# H7.net
KiCad netlist of a schematic drawn in Altium Designer
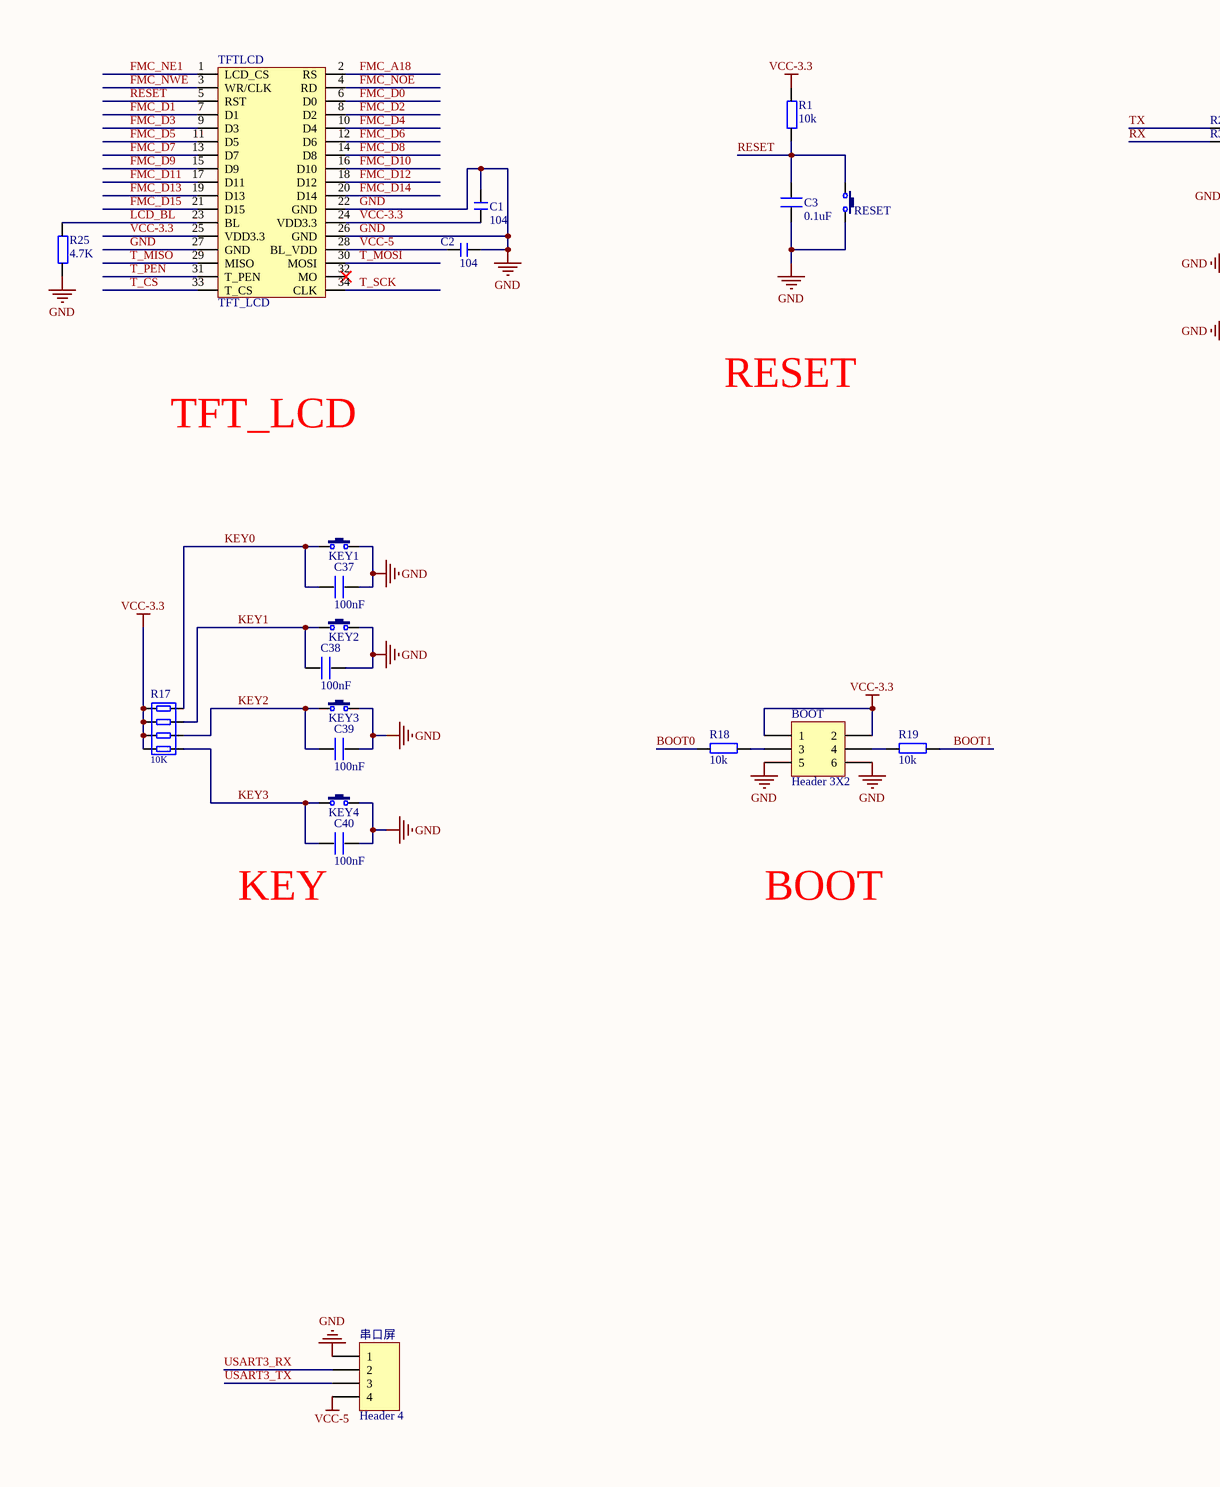
[diagram p0: H7.SchDoc, top left]
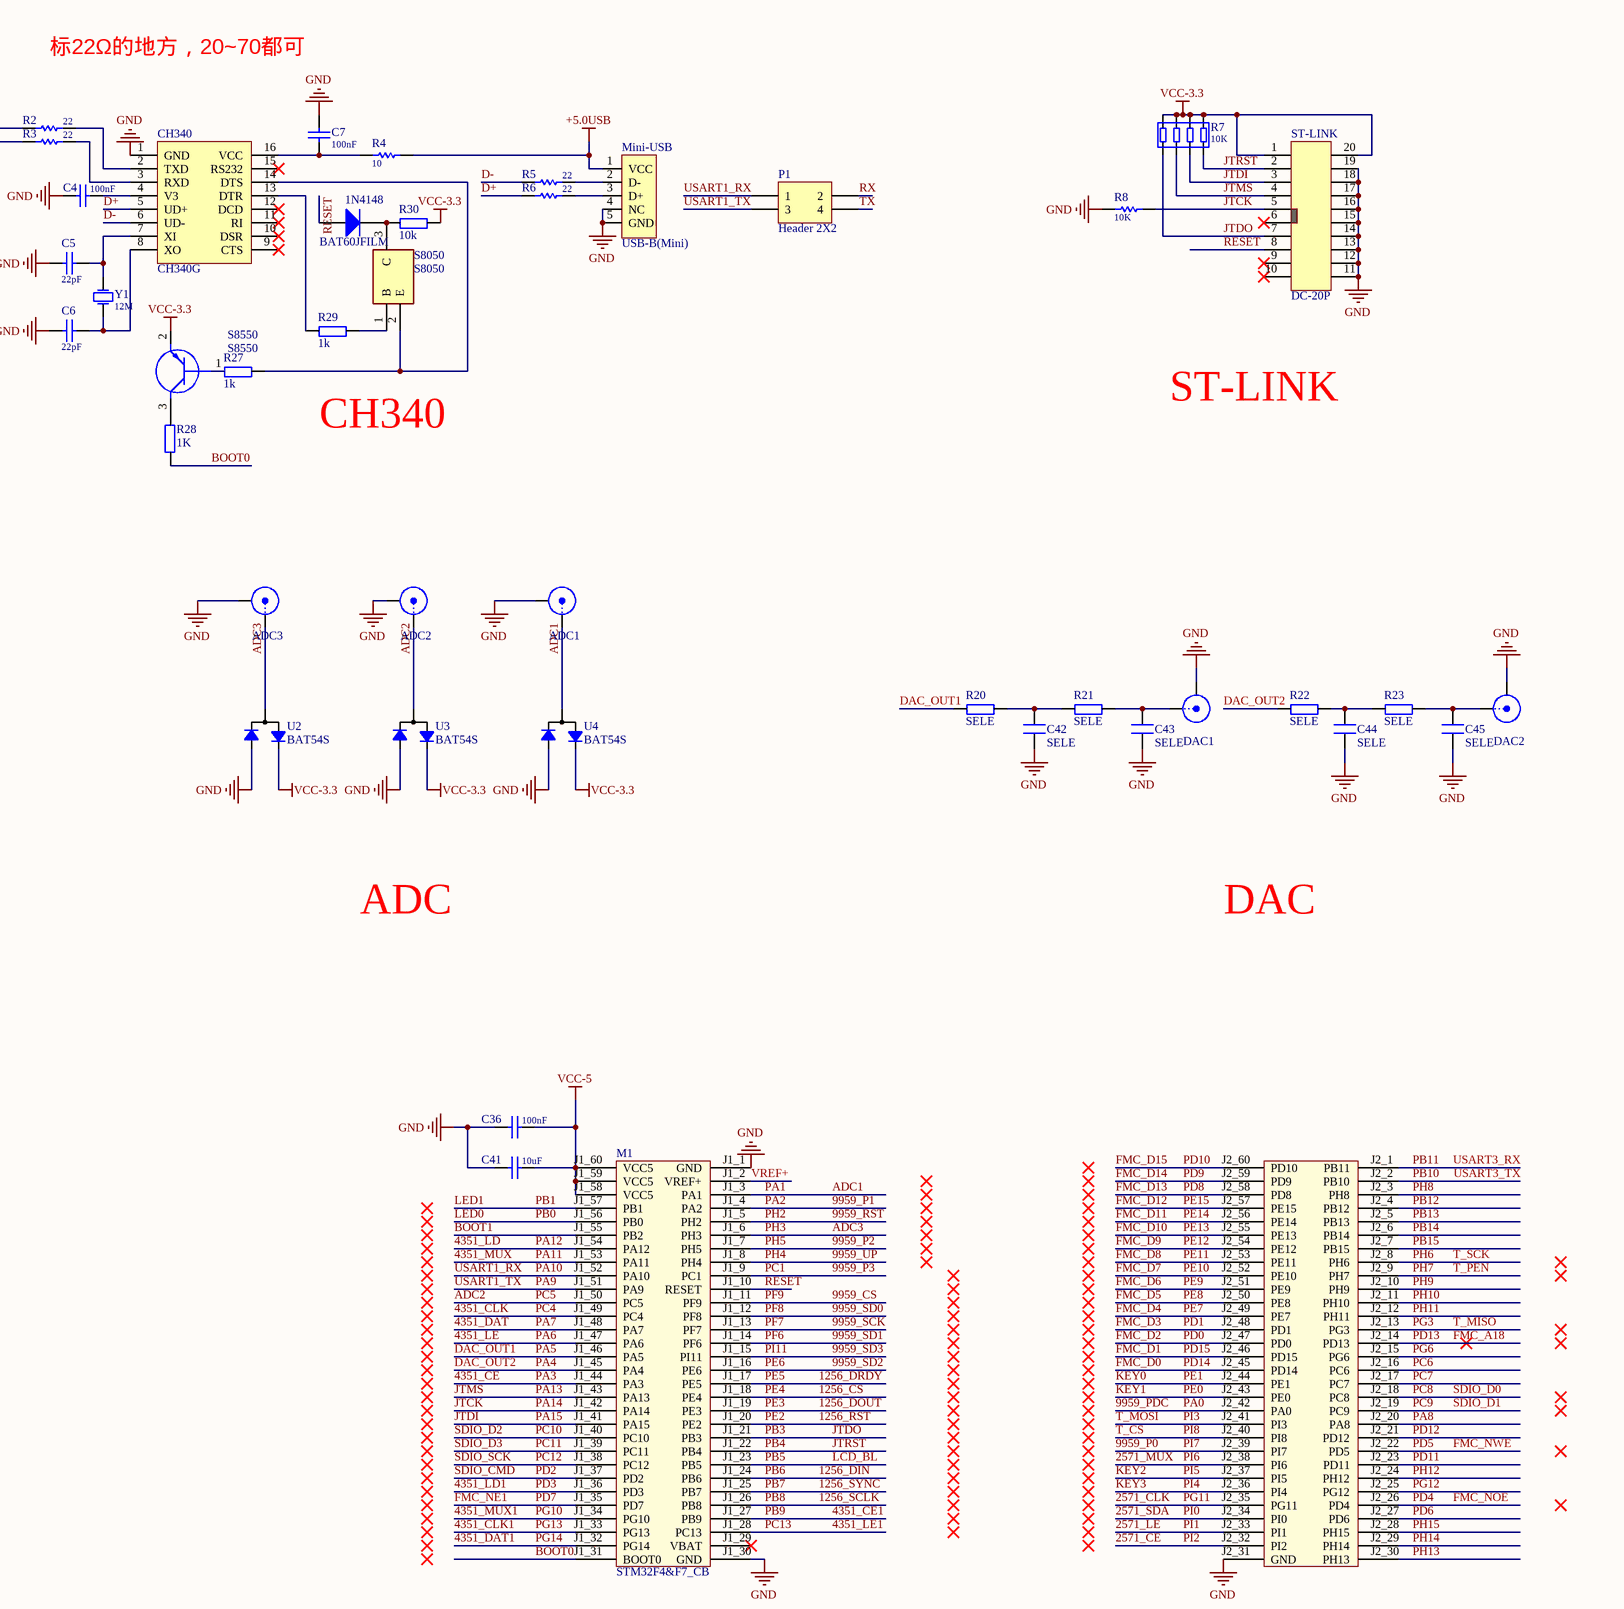
[diagram p1: H7.SchDoc, top middle]
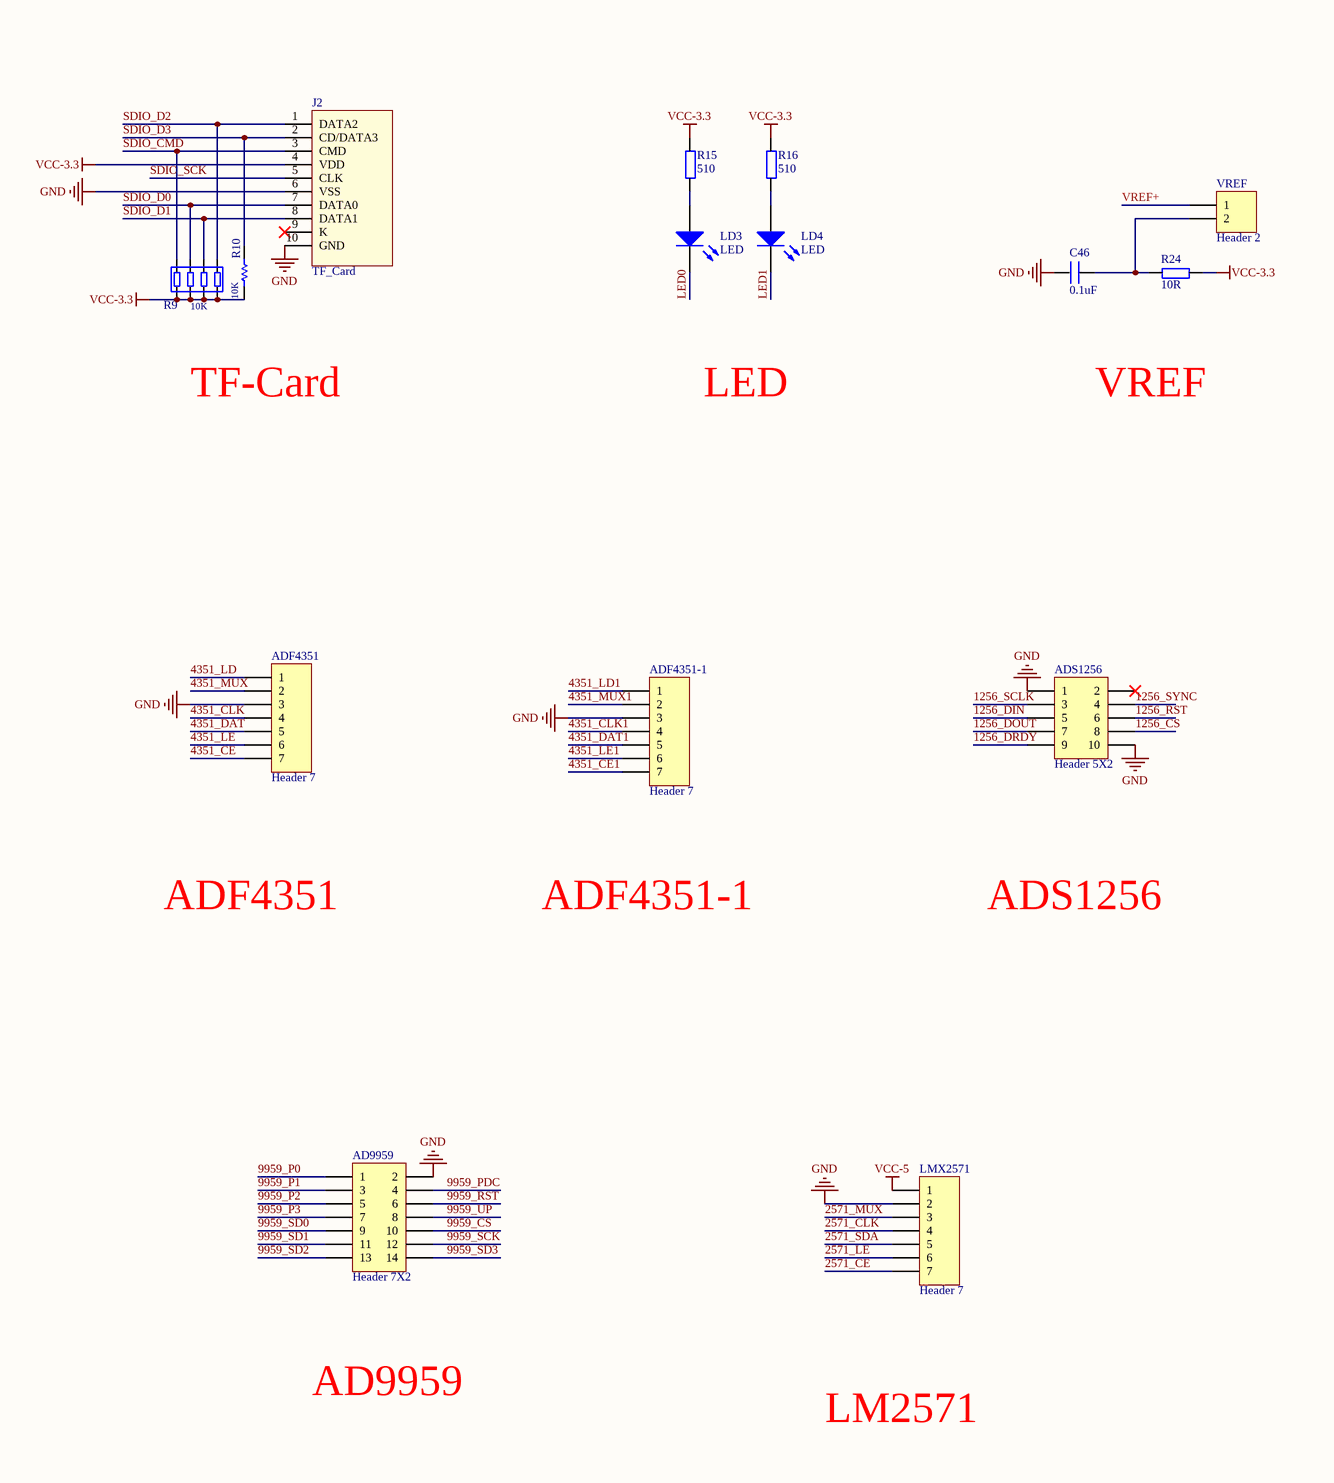
[diagram p2: H7.SchDoc, top right]
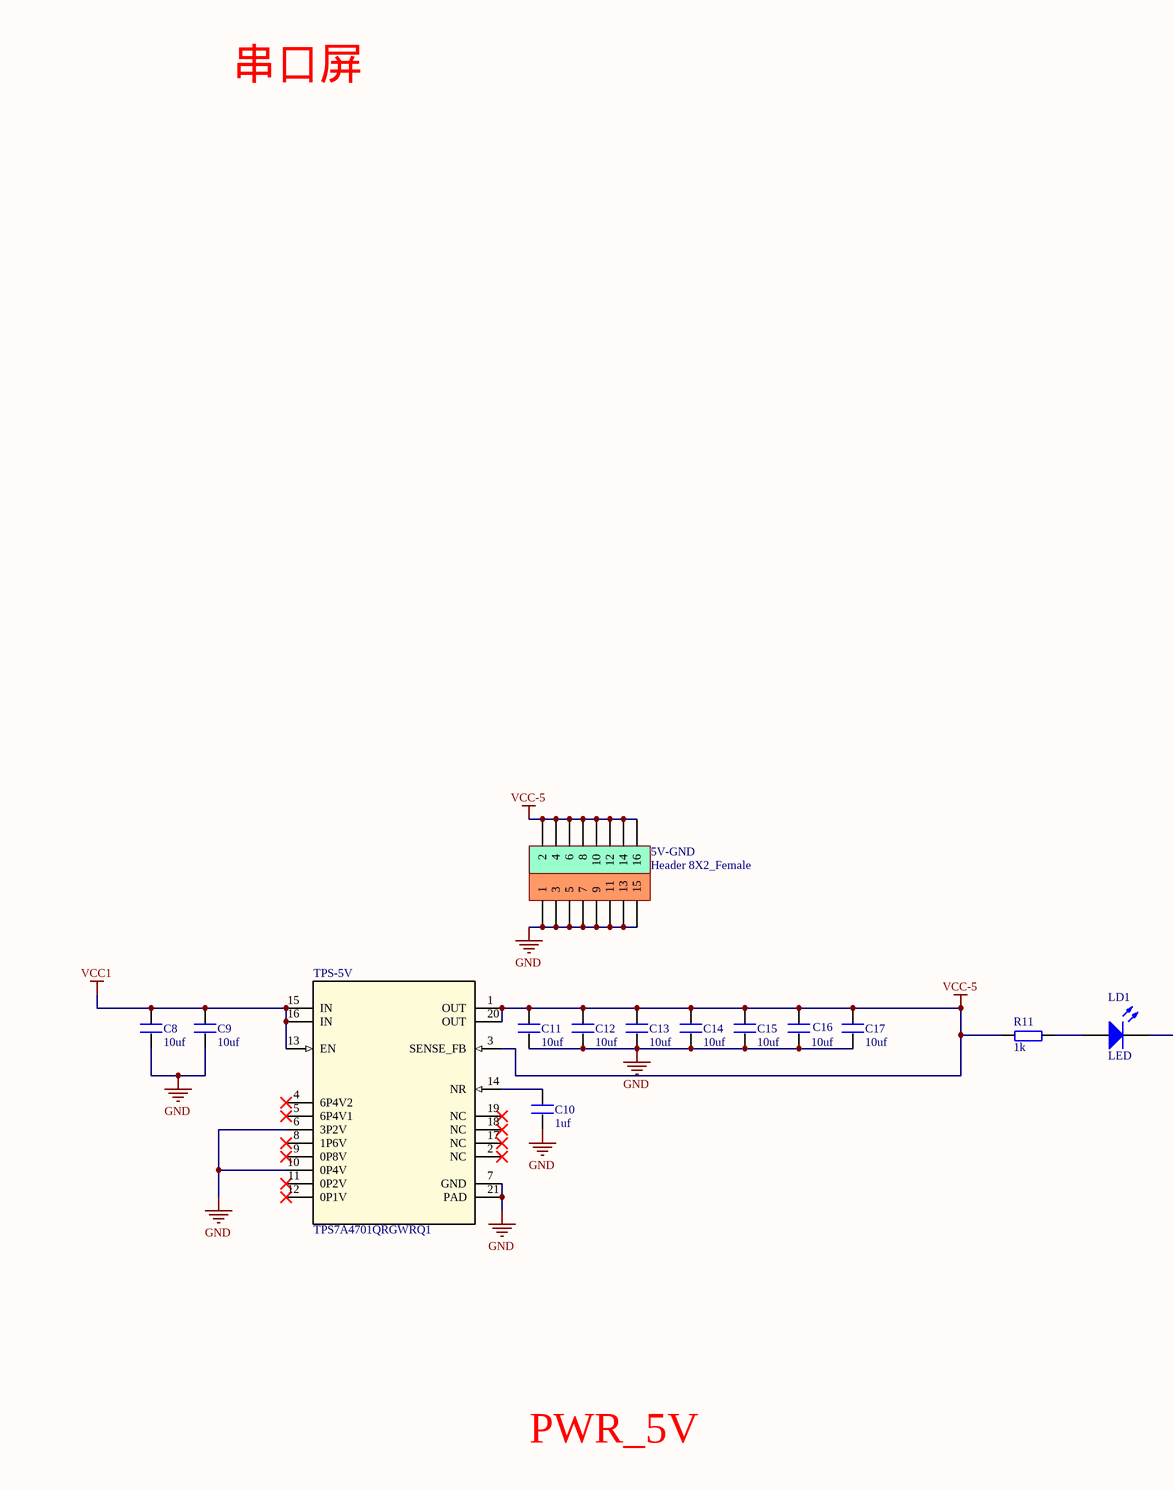
[diagram p3: H7.SchDoc, bottom left]
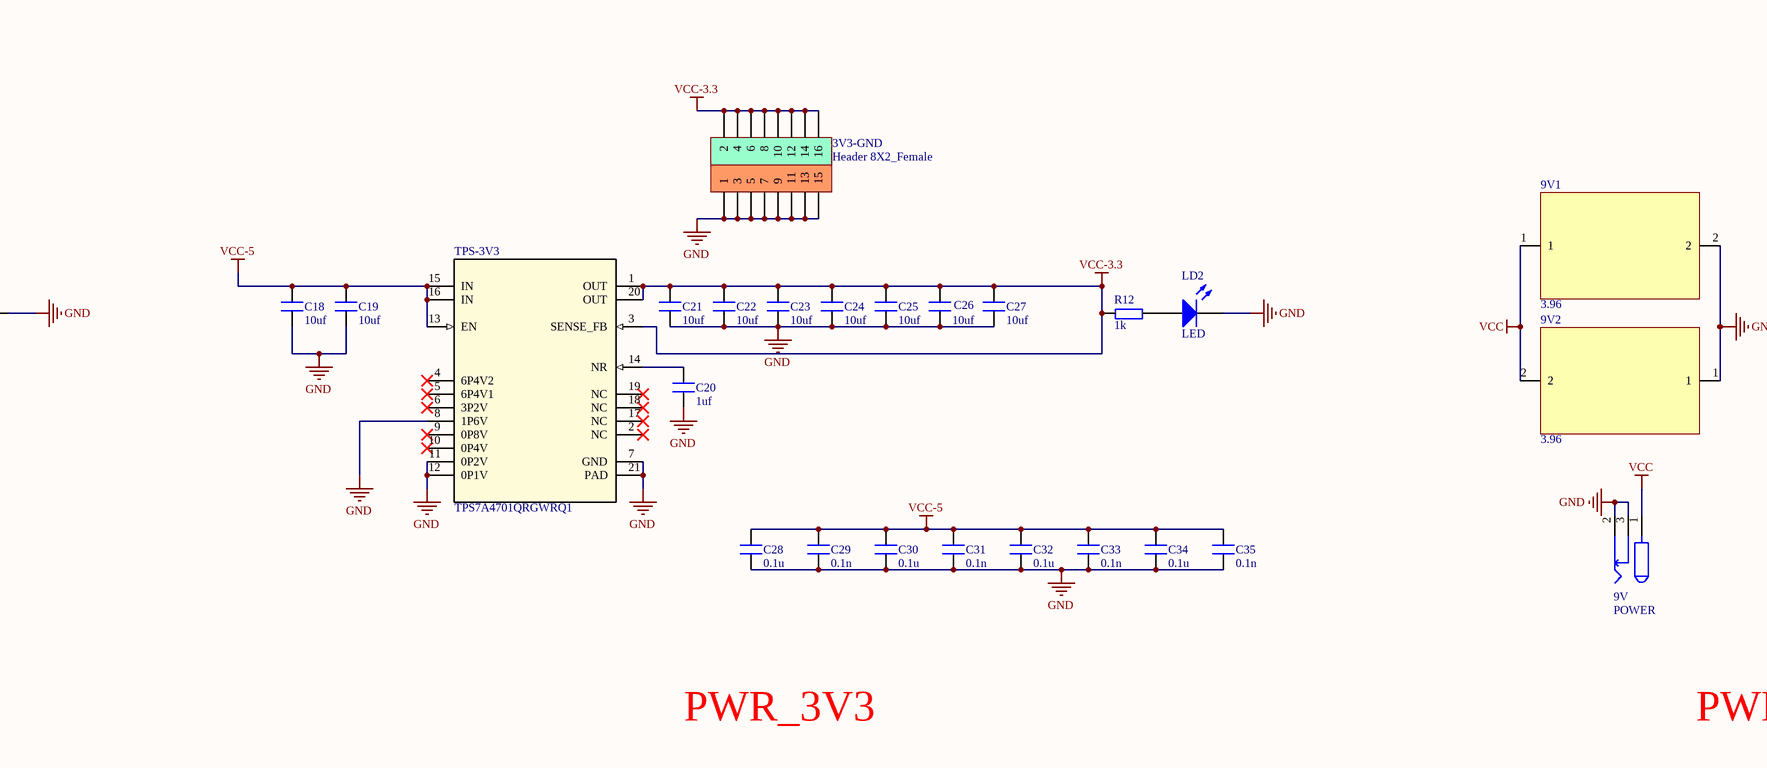
[diagram p4: H7.SchDoc, bottom middle]
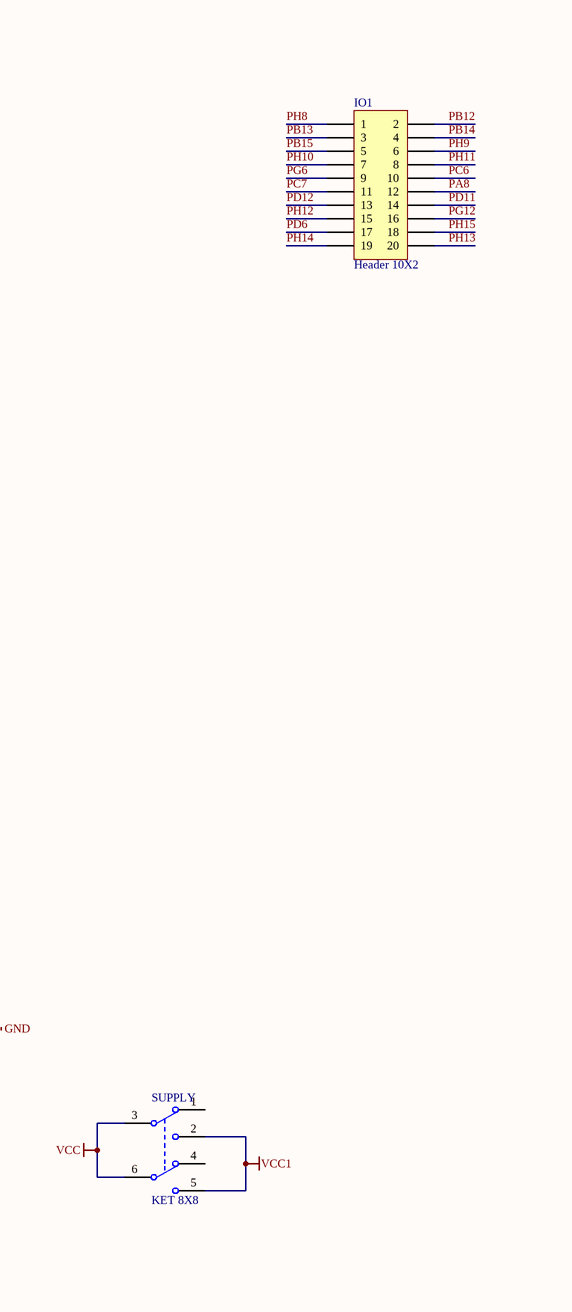
[diagram p5: H7.SchDoc, bottom right]

(export (version "E")
  (design (tool "Eeschema 10.0.6"))
  (components
    (comp (ref "1N4148")
      (value "BAT60JFILM")
      (footprint "DIODE_SOP")
      (description "Default Diode")
      (fields (field (name "PUBLISHER") "Altium Limited"))
      (libsource (lib "MYLIB") (part "Diode"))
    )
    (comp (ref "3V3-GND")
      (value "Header 8X2_Female")
      (footprint "HDR_8x2_2R54_V_F")
      (description "Header, 8-Pin, Dual row,female")
      (fields (field (name "PUBLISHER") "Altium Limited"))
      (libsource (lib "MYLIB") (part "Header 8X2_Female"))
    )
    (comp (ref "5V-GND")
      (value "Header 8X2_Female")
      (footprint "HDR_8x2_2R54_V_F")
      (description "Header, 8-Pin, Dual row,female")
      (fields (field (name "PUBLISHER") "Altium Limited"))
      (libsource (lib "MYLIB") (part "Header 8X2_Female"))
    )
    (comp (ref "9V") (value "POWER") (footprint "DC10B") (libsource (lib "MYLIB") (part "POW")))
    (comp (ref "9V1") (value "3.96") (footprint "3.96") (libsource (lib "MYLIB") (part "3.96")))
    (comp (ref "9V2") (value "3.96") (footprint "3.96") (libsource (lib "") (part "3.96_1")))
    (comp (ref "AD9959")
      (value "Header 7X2")
      (footprint "HDR2X7")
      (description "Header, 7-Pin, Dual row")
      (fields (field (name "PUBLISHER") "Altium Limited"))
      (libsource (lib "Miscellaneous Connectors") (part "Header 7X2"))
    )
    (comp (ref "ADC1")
      (value "SMA")
      (footprint "SMA")
      (description "SMA Connector")
      (libsource (lib "MYLIB") (part "SMA"))
    )
    (comp (ref "ADC2")
      (value "SMA")
      (footprint "SMA")
      (description "SMA Connector")
      (libsource (lib "MYLIB") (part "SMA"))
    )
    (comp (ref "ADC3")
      (value "SMA")
      (footprint "SMA")
      (description "SMA Connector")
      (libsource (lib "MYLIB") (part "SMA"))
    )
    (comp (ref "ADF4351")
      (value "Header 7")
      (footprint "HDR1X7")
      (description "Header, 7-Pin")
      (fields (field (name "PUBLISHER") "Altium Limited"))
      (libsource (lib "Miscellaneous Connectors") (part "Header 7"))
    )
    (comp (ref "ADF4351-1")
      (value "Header 7")
      (footprint "HDR1X7")
      (description "Header, 7-Pin")
      (fields (field (name "PUBLISHER") "Altium Limited"))
      (libsource (lib "Miscellaneous Connectors") (part "Header 7"))
    )
    (comp (ref "ADS1256")
      (value "Header 5X2")
      (footprint "HDR2X5")
      (description "Header, 5-Pin, Dual row")
      (fields (field (name "PUBLISHER") "Altium Limited"))
      (libsource (lib "Miscellaneous Connectors") (part "Header 5X2"))
    )
    (comp (ref "BOOT")
      (value "Header 3X2")
      (footprint "HDR2X3")
      (description "Header, 3-Pin, Dual row")
      (fields (field (name "PUBLISHER") "Altium Limited"))
      (libsource (lib "xz_C") (part "Header 3X2"))
    )
    (comp (ref "C1")
      (value "104")
      (footprint "0603C")
      (description "无极性贴片电容")
      (fields (field (name "版权归属") "源创客"))
      (libsource (lib "3.1   - 电阻-电容-电感") (part "C"))
    )
    (comp (ref "C2")
      (value "104")
      (footprint "0603C")
      (description "无极性贴片电容")
      (fields (field (name "版权归属") "源创客"))
      (libsource (lib "3.1   - 电阻-电容-电感") (part "C"))
    )
    (comp (ref "C3")
      (value "0.1uF")
      (footprint "0603C")
      (description "Capacitor")
      (libsource (lib "MYLIB") (part "C"))
    )
    (comp (ref "C4")
      (value "100nF")
      (footprint "0603C")
      (description "贴片瓷片电容")
      (fields (field (name "Comment") "Cap-S"))
      (libsource (lib "xz_D") (part "Cap-S"))
    )
    (comp (ref "C5")
      (value "22pF")
      (footprint "0603C")
      (description "贴片瓷片电容")
      (fields (field (name "Comment") "Cap-S"))
      (libsource (lib "xz_D") (part "Cap-S"))
    )
    (comp (ref "C6")
      (value "22pF")
      (footprint "0603C")
      (description "贴片瓷片电容")
      (fields (field (name "Comment") "Cap-S"))
      (libsource (lib "xz_D") (part "Cap-S"))
    )
    (comp (ref "C7")
      (value "100nF")
      (footprint "0603C")
      (description "贴片瓷片电容")
      (fields (field (name "Comment") "Cap-S"))
      (libsource (lib "xz_D") (part "Cap-S"))
    )
    (comp (ref "C8")
      (value "10uf")
      (footprint "0603C")
      (description "Capacitor")
      (libsource (lib "MYLIB") (part "C"))
    )
    (comp (ref "C9")
      (value "10uf")
      (footprint "0603C")
      (description "Capacitor")
      (libsource (lib "MYLIB") (part "C"))
    )
    (comp (ref "C10")
      (value "1uf")
      (footprint "0402")
      (description "Capacitor")
      (libsource (lib "MYLIB") (part "C"))
    )
    (comp (ref "C11")
      (value "10uf")
      (footprint "0603C")
      (description "Capacitor")
      (libsource (lib "MYLIB") (part "C"))
    )
    (comp (ref "C12")
      (value "10uf")
      (footprint "0603C")
      (description "Capacitor")
      (libsource (lib "MYLIB") (part "C"))
    )
    (comp (ref "C13")
      (value "10uf")
      (footprint "0603C")
      (description "Capacitor")
      (libsource (lib "MYLIB") (part "C"))
    )
    (comp (ref "C14")
      (value "10uf")
      (footprint "0603C")
      (description "Capacitor")
      (libsource (lib "MYLIB") (part "C"))
    )
    (comp (ref "C15")
      (value "10uf")
      (footprint "0603C")
      (description "Capacitor")
      (libsource (lib "MYLIB") (part "C"))
    )
    (comp (ref "C16")
      (value "10uf")
      (footprint "0603C")
      (description "Capacitor")
      (libsource (lib "MYLIB") (part "C"))
    )
    (comp (ref "C17")
      (value "10uf")
      (footprint "0603C")
      (description "Capacitor")
      (libsource (lib "MYLIB") (part "C"))
    )
    (comp (ref "C18")
      (value "10uf")
      (footprint "0603C")
      (description "Capacitor")
      (libsource (lib "MYLIB") (part "C"))
    )
    (comp (ref "C19")
      (value "10uf")
      (footprint "0603C")
      (description "Capacitor")
      (libsource (lib "MYLIB") (part "C"))
    )
    (comp (ref "C20")
      (value "1uf")
      (footprint "0402")
      (description "Capacitor")
      (libsource (lib "MYLIB") (part "C"))
    )
    (comp (ref "C21")
      (value "10uf")
      (footprint "0603C")
      (description "Capacitor")
      (libsource (lib "MYLIB") (part "C"))
    )
    (comp (ref "C22")
      (value "10uf")
      (footprint "0603C")
      (description "Capacitor")
      (libsource (lib "MYLIB") (part "C"))
    )
    (comp (ref "C23")
      (value "10uf")
      (footprint "0603C")
      (description "Capacitor")
      (libsource (lib "MYLIB") (part "C"))
    )
    (comp (ref "C24")
      (value "10uf")
      (footprint "0603C")
      (description "Capacitor")
      (libsource (lib "MYLIB") (part "C"))
    )
    (comp (ref "C25")
      (value "10uf")
      (footprint "0603C")
      (description "Capacitor")
      (libsource (lib "MYLIB") (part "C"))
    )
    (comp (ref "C26")
      (value "10uf")
      (footprint "0603C")
      (description "Capacitor")
      (libsource (lib "MYLIB") (part "C"))
    )
    (comp (ref "C27")
      (value "10uf")
      (footprint "0603C")
      (description "Capacitor")
      (libsource (lib "MYLIB") (part "C"))
    )
    (comp (ref "C28")
      (value "0.1u")
      (footprint "0402")
      (description "Capacitor")
      (libsource (lib "MYLIB") (part "C"))
    )
    (comp (ref "C29")
      (value "0.1n")
      (footprint "0402")
      (description "Capacitor")
      (libsource (lib "MYLIB") (part "C"))
    )
    (comp (ref "C30")
      (value "0.1u")
      (footprint "0402")
      (description "Capacitor")
      (libsource (lib "MYLIB") (part "C"))
    )
    (comp (ref "C31")
      (value "0.1n")
      (footprint "0402")
      (description "Capacitor")
      (libsource (lib "MYLIB") (part "C"))
    )
    (comp (ref "C32")
      (value "0.1u")
      (footprint "0402")
      (description "Capacitor")
      (libsource (lib "MYLIB") (part "C"))
    )
    (comp (ref "C33")
      (value "0.1n")
      (footprint "0402")
      (description "Capacitor")
      (libsource (lib "MYLIB") (part "C"))
    )
    (comp (ref "C34")
      (value "0.1u")
      (footprint "0402")
      (description "Capacitor")
      (libsource (lib "MYLIB") (part "C"))
    )
    (comp (ref "C35")
      (value "0.1n")
      (footprint "0402")
      (description "Capacitor")
      (libsource (lib "MYLIB") (part "C"))
    )
    (comp (ref "C36")
      (value "100nF")
      (footprint "C0603-L")
      (description "贴片瓷片电容")
      (fields (field (name "Comment") "Cap-S"))
      (libsource (lib "xz_D") (part "Cap-S"))
    )
    (comp (ref "C37")
      (value "100nF")
      (footprint "0603C")
      (description "Capacitor")
      (libsource (lib "MYLIB") (part "C"))
    )
    (comp (ref "C38")
      (value "100nF")
      (footprint "0603C")
      (description "Capacitor")
      (libsource (lib "MYLIB") (part "C"))
    )
    (comp (ref "C39")
      (value "100nF")
      (footprint "0603C")
      (description "Capacitor")
      (libsource (lib "MYLIB") (part "C"))
    )
    (comp (ref "C40")
      (value "100nF")
      (footprint "0603C")
      (description "Capacitor")
      (libsource (lib "MYLIB") (part "C"))
    )
    (comp (ref "C41")
      (value "10uF")
      (footprint "0603C")
      (description "贴片瓷片电容")
      (fields (field (name "Comment") "Cap-S"))
      (libsource (lib "xz_D") (part "Cap-S"))
    )
    (comp (ref "C42")
      (value "SELE")
      (footprint "0603C")
      (description "Capacitor")
      (libsource (lib "MYLIB") (part "C"))
    )
    (comp (ref "C43")
      (value "SELE")
      (footprint "0603C")
      (description "Capacitor")
      (libsource (lib "MYLIB") (part "C"))
    )
    (comp (ref "C44")
      (value "SELE")
      (footprint "0603C")
      (description "Capacitor")
      (libsource (lib "MYLIB") (part "C"))
    )
    (comp (ref "C45")
      (value "SELE")
      (footprint "0603C")
      (description "Capacitor")
      (libsource (lib "MYLIB") (part "C"))
    )
    (comp (ref "C46")
      (value "0.1uF")
      (footprint "0603C")
      (description "Capacitor")
      (libsource (lib "MYLIB") (part "C"))
    )
    (comp (ref "CH340")
      (value "CH340G")
      (footprint "SOP-16")
      (description "SOP16")
      (libsource (lib "CommonUsed") (part "CH340G"))
    )
    (comp (ref "DAC1")
      (value "SMA")
      (footprint "SMA")
      (description "SMA Connector")
      (libsource (lib "MYLIB") (part "SMA"))
    )
    (comp (ref "DAC2")
      (value "SMA")
      (footprint "SMA")
      (description "SMA Connector")
      (libsource (lib "MYLIB") (part "SMA"))
    )
    (comp (ref "IO1")
      (value "Header 10X2")
      (footprint "HDR2X10")
      (description "Header, 10-Pin, Dual row")
      (fields (field (name "PUBLISHER") "Altium Limited"))
      (libsource (lib "Miscellaneous Connectors") (part "Header 10X2"))
    )
    (comp (ref "J2")
      (value "TF_Card")
      (footprint "Micro SD")
      (description "TF卡座")
      (fields (field (name "版权归属") "源创客"))
      (libsource (lib "4.1   - 接口类") (part "TF_Card"))
    )
    (comp (ref "KEY1")
      (value "3x6x5")
      (footprint "TSW SMD-3*6*2.5")
      (description "3x6轻触开关")
      (fields (field (name "版权归属") "源创客"))
      (libsource (lib "") (part "TSW 3x6_1"))
    )
    (comp (ref "KEY2")
      (value "3x6x5")
      (footprint "TSW SMD-3*6*2.5")
      (description "3x6轻触开关")
      (fields (field (name "版权归属") "源创客"))
      (libsource (lib "") (part "TSW 3x6_1"))
    )
    (comp (ref "KEY3")
      (value "3x6x5")
      (footprint "TSW SMD-3*6*2.5")
      (description "3x6轻触开关")
      (fields (field (name "版权归属") "源创客"))
      (libsource (lib "") (part "TSW 3x6_1"))
    )
    (comp (ref "KEY4")
      (value "3x6x5")
      (footprint "TSW SMD-3*6*2.5")
      (description "3x6轻触开关")
      (fields (field (name "版权归属") "源创客"))
      (libsource (lib "") (part "TSW 3x6_1"))
    )
    (comp (ref "LD1")
      (value "LED")
      (footprint "SMDLED")
      (description "Typical RED, GREEN, YELLOW, AMBER GaAs LED")
      (fields (field (name "PUBLISHER") "Altium Limited"))
      (libsource (lib "MYLIB") (part "LED"))
    )
    (comp (ref "LD2")
      (value "LED")
      (footprint "SMDLED")
      (description "Typical RED, GREEN, YELLOW, AMBER GaAs LED")
      (fields (field (name "PUBLISHER") "Altium Limited"))
      (libsource (lib "MYLIB") (part "LED"))
    )
    (comp (ref "LD3")
      (value "LED")
      (footprint "SMDLED")
      (description "Typical RED, GREEN, YELLOW, AMBER GaAs LED")
      (fields (field (name "PUBLISHER") "Altium Limited"))
      (libsource (lib "MYLIB") (part "LED"))
    )
    (comp (ref "LD4")
      (value "LED")
      (footprint "SMDLED")
      (description "Typical RED, GREEN, YELLOW, AMBER GaAs LED")
      (fields (field (name "PUBLISHER") "Altium Limited"))
      (libsource (lib "MYLIB") (part "LED"))
    )
    (comp (ref "LMX2571")
      (value "Header 7")
      (footprint "HDR1X7")
      (description "Header, 7-Pin")
      (fields (field (name "PUBLISHER") "Altium Limited"))
      (libsource (lib "Miscellaneous Connectors") (part "Header 7"))
    )
    (comp (ref "M1")
      (value "STM32F4&F7_CB")
      (footprint "STM32F4&F7_CB - duplicate")
      (description "F429/746 Core Board")
      (libsource (lib "STM32H7-Board") (part "STM32F4&F7_CB"))
    )
    (comp (ref "Mini-USB")
      (value "USB-B(Mini)")
      (footprint "USB/SM0.8-6H5")
      (libsource (lib "MYLIB") (part "USB5"))
    )
    (comp (ref "P1")
      (value "Header 2X2")
      (footprint "HDR2X2")
      (description "Header, 2-Pin, Dual row")
      (fields (field (name "PUBLISHER") "Altium Limited"))
      (libsource (lib "MYLIB") (part "Header 2X2"))
    )
    (comp (ref "R1")
      (value "10k")
      (footprint "0603R")
      (description "Resistor")
      (libsource (lib "MYLIB") (part "Resistor"))
    )
    (comp (ref "R2")
      (value "22")
      (footprint "0603R")
      (description "贴片电阻")
      (fields (field (name "Comment") "R"))
      (libsource (lib "xz_D") (part "Res"))
    )
    (comp (ref "R3")
      (value "22")
      (footprint "0603R")
      (description "贴片电阻")
      (fields (field (name "Comment") "R"))
      (libsource (lib "xz_D") (part "Res"))
    )
    (comp (ref "R4")
      (value "10")
      (footprint "0603R")
      (description "贴片电阻")
      (fields (field (name "Comment") "R"))
      (libsource (lib "xz_D") (part "Res"))
    )
    (comp (ref "R5")
      (value "22")
      (footprint "0603R")
      (description "贴片电阻")
      (fields (field (name "Comment") "R"))
      (libsource (lib "xz_D") (part "Res"))
    )
    (comp (ref "R6")
      (value "22")
      (footprint "0603R")
      (description "贴片电阻")
      (fields (field (name "Comment") "R"))
      (libsource (lib "xz_D") (part "Res"))
    )
    (comp (ref "R7")
      (value "10K")
      (footprint "R0603X4")
      (description "排阻 4")
      (fields (field (name "Comment") "R"))
      (libsource (lib "xz_D") (part "Res-4R"))
    )
    (comp (ref "R8")
      (value "10K")
      (footprint "0603R")
      (description "贴片电阻")
      (fields (field (name "Comment") "R"))
      (libsource (lib "xz_D") (part "Res"))
    )
    (comp (ref "R9")
      (value "10K")
      (footprint "R0603X4")
      (description "排阻 4")
      (fields (field (name "Comment") "R"))
      (libsource (lib "xz_D") (part "Res-4R"))
    )
    (comp (ref "R10")
      (value "10K")
      (footprint "0603R")
      (description "贴片电阻")
      (fields (field (name "Comment") "R"))
      (libsource (lib "xz_D") (part "Res"))
    )
    (comp (ref "R11")
      (value "1k")
      (footprint "0603R")
      (description "Resistor")
      (libsource (lib "MYLIB") (part "Resistor"))
    )
    (comp (ref "R12")
      (value "1k")
      (footprint "0603R")
      (description "Resistor")
      (libsource (lib "MYLIB") (part "Resistor"))
    )
    (comp (ref "R15")
      (value "510")
      (footprint "0603R")
      (description "Resistor")
      (libsource (lib "MYLIB") (part "Resistor"))
    )
    (comp (ref "R16")
      (value "510")
      (footprint "0603R")
      (description "Resistor")
      (libsource (lib "MYLIB") (part "Resistor"))
    )
    (comp (ref "R17")
      (value "10K")
      (footprint "R0603X4")
      (description "排阻 4")
      (fields (field (name "Comment") "R"))
      (libsource (lib "xz_D") (part "Res-4R"))
    )
    (comp (ref "R18")
      (value "10k")
      (footprint "0603R")
      (description "Resistor")
      (libsource (lib "MYLIB") (part "Resistor"))
    )
    (comp (ref "R19")
      (value "10k")
      (footprint "0603R")
      (description "Resistor")
      (libsource (lib "MYLIB") (part "Resistor"))
    )
    (comp (ref "R20")
      (value "SELE")
      (footprint "0603R")
      (description "Resistor")
      (libsource (lib "MYLIB") (part "Resistor"))
    )
    (comp (ref "R21")
      (value "SELE")
      (footprint "0603R")
      (description "Resistor")
      (libsource (lib "MYLIB") (part "Resistor"))
    )
    (comp (ref "R22")
      (value "SELE")
      (footprint "0603R")
      (description "Resistor")
      (libsource (lib "MYLIB") (part "Resistor"))
    )
    (comp (ref "R23")
      (value "SELE")
      (footprint "0603R")
      (description "Resistor")
      (libsource (lib "MYLIB") (part "Resistor"))
    )
    (comp (ref "R24")
      (value "10R")
      (footprint "0603R")
      (description "Resistor")
      (libsource (lib "MYLIB") (part "Resistor"))
    )
    (comp (ref "R25")
      (value "4.7K")
      (footprint "0603R")
      (description "Resistor")
      (libsource (lib "MYLIB") (part "Resistor"))
    )
    (comp (ref "R27")
      (value "1k")
      (footprint "0603R")
      (description "Resistor")
      (libsource (lib "MYLIB") (part "Resistor"))
    )
    (comp (ref "R28")
      (value "1K")
      (footprint "0603R")
      (description "Resistor")
      (libsource (lib "MYLIB") (part "Resistor"))
    )
    (comp (ref "R29")
      (value "1k")
      (footprint "0603R")
      (description "Resistor")
      (libsource (lib "MYLIB") (part "Resistor"))
    )
    (comp (ref "R30")
      (value "10k")
      (footprint "0603R")
      (description "Resistor")
      (libsource (lib "MYLIB") (part "Resistor"))
    )
    (comp (ref "RESET")
      (value "3x6x5")
      (footprint "TSW SMD-3*6*2.5")
      (description "3x6轻触开关")
      (fields (field (name "版权归属") "源创客"))
      (libsource (lib "MYLIB") (part "TSW 3x6"))
    )
    (comp (ref "S8050")
      (value "S8050")
      (footprint "MYLIB:SOT95P240X115-3N")
      (description "Transistor")
      (libsource (lib "*") (part "S8050"))
    )
    (comp (ref "S8550")
      (value "S8550")
      (footprint "MYLIB:SOT95P240X115-3N")
      (description "Transistor BJT PNP")
      (libsource (lib "*") (part "S8550"))
    )
    (comp (ref "ST-LINK")
      (value "DC-20P")
      (footprint "DC-20P")
      (libsource (lib "CommonUsed") (part "DC-20P"))
    )
    (comp (ref "SUPPLY")
      (value "KET 8X8")
      (footprint "KFT DIP-8X8")
      (description "8*8自锁开关")
      (fields (field (name "版权归属") "源创客"))
      (libsource (lib "MYLIB") (part "KET 8X8"))
    )
    (comp (ref "TFTLCD")
      (value "TFT_LCD")
      (footprint "db2*17-4.3")
      (libsource (lib "MERCURY") (part "TFT_LCD"))
    )
    (comp (ref "TPS-3V3")
      (value "TPS7A4701QRGWRQ1")
      (footprint "RGW0020A")
      (description "No Description Available")
      (fields
        (field (name "MANUFACTURER") "Texas Instruments")
        (field (name "COPYRIGHT") "Copyright (C) 2018 Accelerated Designs. All rights reserved")
      )
      (libsource (lib "MYLIB") (part "TPS7A4701QRGWRQ1"))
    )
    (comp (ref "TPS-5V")
      (value "TPS7A4701QRGWRQ1")
      (footprint "RGW0020A")
      (description "No Description Available")
      (fields
        (field (name "MANUFACTURER") "Texas Instruments")
        (field (name "COPYRIGHT") "Copyright (C) 2018 Accelerated Designs. All rights reserved")
      )
      (libsource (lib "MYLIB") (part "TPS7A4701QRGWRQ1"))
    )
    (comp (ref "U2") (value "BAT54S") (footprint "SOT-23-3") (libsource (lib "xuxuxu") (part "BAT54S")))
    (comp (ref "U3") (value "BAT54S") (footprint "SOT-23-3") (libsource (lib "xuxuxu") (part "BAT54S")))
    (comp (ref "U4") (value "BAT54S") (footprint "SOT-23-3") (libsource (lib "xuxuxu") (part "BAT54S")))
    (comp (ref "VREF")
      (value "Header 2")
      (footprint "HDR1X2")
      (description "Header, 2-Pin")
      (fields (field (name "PUBLISHER") "Altium Limited"))
      (libsource (lib "Miscellaneous Connectors") (part "Header 2"))
    )
    (comp (ref "Y1")
      (value "12M")
      (footprint "XTAL-PB2-SMD")
      (description "晶振")
      (fields (field (name "Comment") "XTAL"))
      (libsource (lib "CommonUsed") (part "XTAL"))
    )
    (comp (ref "串口屏")
      (value "Header 4")
      (footprint "HDR1X4")
      (description "Header, 4-Pin")
      (fields (field (name "PUBLISHER") "Altium Limited"))
      (libsource (lib "Miscellaneous Connectors") (part "Header 4"))
    )
  )
  (nets
    (net (code "1") (name "+5.0USB") (class "Default")
      (node (ref "Mini-USB") (pin "1") (pinfunction "VCC_1") (pintype "passive"))
      (node (ref "R4") (pin "1") (pinfunction "1_1") (pintype "passive"))
    )
    (net (code "2") (name "/1256_CS") (class "Default")
      (node (ref "ADS1256") (pin "8") (pinfunction "8_8") (pintype "passive"))
      (node (ref "M1") (pin "J1_18") (pinfunction "PE4_J1_18") (pintype "passive"))
    )
    (net (code "3") (name "/1256_DIN") (class "Default")
      (node (ref "ADS1256") (pin "5") (pinfunction "5_5") (pintype "passive"))
      (node (ref "M1") (pin "J1_24") (pinfunction "PB6_J1_24") (pintype "passive"))
    )
    (net (code "4") (name "/1256_DOUT") (class "Default")
      (node (ref "ADS1256") (pin "7") (pinfunction "7_7") (pintype "passive"))
      (node (ref "M1") (pin "J1_19") (pinfunction "PE3_J1_19") (pintype "passive"))
    )
    (net (code "5") (name "/1256_DRDY") (class "Default")
      (node (ref "ADS1256") (pin "9") (pinfunction "9_9") (pintype "passive"))
      (node (ref "M1") (pin "J1_17") (pinfunction "PE5_J1_17") (pintype "passive"))
    )
    (net (code "6") (name "/1256_RST") (class "Default")
      (node (ref "ADS1256") (pin "6") (pinfunction "6_6") (pintype "passive"))
      (node (ref "M1") (pin "J1_20") (pinfunction "PE2_J1_20") (pintype "passive"))
    )
    (net (code "7") (name "/1256_SCLK") (class "Default")
      (node (ref "ADS1256") (pin "3") (pinfunction "3_3") (pintype "passive"))
      (node (ref "M1") (pin "J1_26") (pinfunction "PB8_J1_26") (pintype "passive"))
    )
    (net (code "8") (name "/1256_SYNC") (class "Default")
      (node (ref "ADS1256") (pin "4") (pinfunction "4_4") (pintype "passive"))
      (node (ref "M1") (pin "J1_25") (pinfunction "PB7_J1_25") (pintype "passive"))
    )
    (net (code "9") (name "/2571_CE") (class "Default")
      (node (ref "LMX2571") (pin "7") (pinfunction "7_7") (pintype "passive"))
      (node (ref "M1") (pin "J2_32") (pinfunction "PI2_J2_32") (pintype "passive"))
    )
    (net (code "10") (name "/2571_CLK") (class "Default")
      (node (ref "LMX2571") (pin "4") (pinfunction "4_4") (pintype "passive"))
      (node (ref "M1") (pin "J2_35") (pinfunction "PG11_J2_35") (pintype "passive"))
    )
    (net (code "11") (name "/2571_LE") (class "Default")
      (node (ref "LMX2571") (pin "6") (pinfunction "6_6") (pintype "passive"))
      (node (ref "M1") (pin "J2_33") (pinfunction "PI1_J2_33") (pintype "passive"))
    )
    (net (code "12") (name "/2571_MUX") (class "Default")
      (node (ref "LMX2571") (pin "3") (pinfunction "3_3") (pintype "passive"))
      (node (ref "M1") (pin "J2_38") (pinfunction "PI6_J2_38") (pintype "passive"))
    )
    (net (code "13") (name "/2571_SDA") (class "Default")
      (node (ref "LMX2571") (pin "5") (pinfunction "5_5") (pintype "passive"))
      (node (ref "M1") (pin "J2_34") (pinfunction "PI0_J2_34") (pintype "passive"))
    )
    (net (code "14") (name "/4351_CE") (class "Default")
      (node (ref "ADF4351") (pin "7") (pinfunction "7_7") (pintype "passive"))
      (node (ref "M1") (pin "J1_44") (pinfunction "PA3_J1_44") (pintype "passive"))
    )
    (net (code "15") (name "/4351_CE1") (class "Default")
      (node (ref "ADF4351-1") (pin "7") (pinfunction "7_7") (pintype "passive"))
      (node (ref "M1") (pin "J1_27") (pinfunction "PB9_J1_27") (pintype "passive"))
    )
    (net (code "16") (name "/4351_CLK") (class "Default")
      (node (ref "ADF4351") (pin "4") (pinfunction "4_4") (pintype "passive"))
      (node (ref "M1") (pin "J1_49") (pinfunction "PC4_J1_49") (pintype "passive"))
    )
    (net (code "17") (name "/4351_CLK1") (class "Default")
      (node (ref "ADF4351-1") (pin "4") (pinfunction "4_4") (pintype "passive"))
      (node (ref "M1") (pin "J1_33") (pinfunction "PG13_J1_33") (pintype "passive"))
    )
    (net (code "18") (name "/4351_DAT") (class "Default")
      (node (ref "ADF4351") (pin "5") (pinfunction "5_5") (pintype "passive"))
      (node (ref "M1") (pin "J1_48") (pinfunction "PA7_J1_48") (pintype "passive"))
    )
    (net (code "19") (name "/4351_DAT1") (class "Default")
      (node (ref "ADF4351-1") (pin "5") (pinfunction "5_5") (pintype "passive"))
      (node (ref "M1") (pin "J1_32") (pinfunction "PG14_J1_32") (pintype "passive"))
    )
    (net (code "20") (name "/4351_LD") (class "Default")
      (node (ref "ADF4351") (pin "1") (pinfunction "1_1") (pintype "passive"))
      (node (ref "M1") (pin "J1_54") (pinfunction "PA12_J1_54") (pintype "passive"))
    )
    (net (code "21") (name "/4351_LD1") (class "Default")
      (node (ref "ADF4351-1") (pin "1") (pinfunction "1_1") (pintype "passive"))
      (node (ref "M1") (pin "J1_36") (pinfunction "PD3_J1_36") (pintype "passive"))
    )
    (net (code "22") (name "/4351_LE") (class "Default")
      (node (ref "ADF4351") (pin "6") (pinfunction "6_6") (pintype "passive"))
      (node (ref "M1") (pin "J1_47") (pinfunction "PA6_J1_47") (pintype "passive"))
    )
    (net (code "23") (name "/4351_LE1") (class "Default")
      (node (ref "ADF4351-1") (pin "6") (pinfunction "6_6") (pintype "passive"))
      (node (ref "M1") (pin "J1_28") (pinfunction "PC13_J1_28") (pintype "passive"))
    )
    (net (code "24") (name "/4351_MUX") (class "Default")
      (node (ref "ADF4351") (pin "2") (pinfunction "2_2") (pintype "passive"))
      (node (ref "M1") (pin "J1_53") (pinfunction "PA11_J1_53") (pintype "passive"))
    )
    (net (code "25") (name "/4351_MUX1") (class "Default")
      (node (ref "ADF4351-1") (pin "2") (pinfunction "2_2") (pintype "passive"))
      (node (ref "M1") (pin "J1_34") (pinfunction "PG10_J1_34") (pintype "passive"))
    )
    (net (code "26") (name "/9959_CS") (class "Default")
      (node (ref "AD9959") (pin "10") (pinfunction "10_10") (pintype "passive"))
      (node (ref "M1") (pin "J1_11") (pinfunction "PF9_J1_11") (pintype "passive"))
    )
    (net (code "27") (name "/9959_P0") (class "Default")
      (node (ref "AD9959") (pin "1") (pinfunction "1_1") (pintype "passive"))
      (node (ref "M1") (pin "J2_39") (pinfunction "PI7_J2_39") (pintype "passive"))
    )
    (net (code "28") (name "/9959_P1") (class "Default")
      (node (ref "AD9959") (pin "3") (pinfunction "3_3") (pintype "passive"))
      (node (ref "M1") (pin "J1_4") (pinfunction "PA2_J1_4") (pintype "passive"))
    )
    (net (code "29") (name "/9959_P2") (class "Default")
      (node (ref "AD9959") (pin "5") (pinfunction "5_5") (pintype "passive"))
      (node (ref "M1") (pin "J1_7") (pinfunction "PH5_J1_7") (pintype "passive"))
    )
    (net (code "30") (name "/9959_P3") (class "Default")
      (node (ref "AD9959") (pin "7") (pinfunction "7_7") (pintype "passive"))
      (node (ref "M1") (pin "J1_9") (pinfunction "PC1_J1_9") (pintype "passive"))
    )
    (net (code "31") (name "/9959_PDC") (class "Default")
      (node (ref "AD9959") (pin "4") (pinfunction "4_4") (pintype "passive"))
      (node (ref "M1") (pin "J2_42") (pinfunction "PA0_J2_42") (pintype "passive"))
    )
    (net (code "32") (name "/9959_RST") (class "Default")
      (node (ref "AD9959") (pin "6") (pinfunction "6_6") (pintype "passive"))
      (node (ref "M1") (pin "J1_5") (pinfunction "PH2_J1_5") (pintype "passive"))
    )
    (net (code "33") (name "/9959_SCK") (class "Default")
      (node (ref "AD9959") (pin "12") (pinfunction "12_12") (pintype "passive"))
      (node (ref "M1") (pin "J1_13") (pinfunction "PF7_J1_13") (pintype "passive"))
    )
    (net (code "34") (name "/9959_SD0") (class "Default")
      (node (ref "AD9959") (pin "9") (pinfunction "9_9") (pintype "passive"))
      (node (ref "M1") (pin "J1_12") (pinfunction "PF8_J1_12") (pintype "passive"))
    )
    (net (code "35") (name "/9959_SD1") (class "Default")
      (node (ref "AD9959") (pin "11") (pinfunction "11_11") (pintype "passive"))
      (node (ref "M1") (pin "J1_14") (pinfunction "PF6_J1_14") (pintype "passive"))
    )
    (net (code "36") (name "/9959_SD2") (class "Default")
      (node (ref "AD9959") (pin "13") (pinfunction "13_13") (pintype "passive"))
      (node (ref "M1") (pin "J1_16") (pinfunction "PE6_J1_16") (pintype "passive"))
    )
    (net (code "37") (name "/9959_SD3") (class "Default")
      (node (ref "AD9959") (pin "14") (pinfunction "14_14") (pintype "passive"))
      (node (ref "M1") (pin "J1_15") (pinfunction "PI11_J1_15") (pintype "passive"))
    )
    (net (code "38") (name "/9959_UP") (class "Default")
      (node (ref "AD9959") (pin "8") (pinfunction "8_8") (pintype "passive"))
      (node (ref "M1") (pin "J1_8") (pinfunction "PH4_J1_8") (pintype "passive"))
    )
    (net (code "39") (name "/ADC1") (class "Default")
      (node (ref "ADC1") (pin "1") (pinfunction "X_1") (pintype "passive"))
      (node (ref "M1") (pin "J1_3") (pinfunction "PA1_J1_3") (pintype "passive"))
      (node (ref "U4") (pin "2") (pinfunction "2_2") (pintype "passive"))
    )
    (net (code "40") (name "/ADC2") (class "Default")
      (node (ref "ADC2") (pin "1") (pinfunction "X_1") (pintype "passive"))
      (node (ref "M1") (pin "J1_50") (pinfunction "PC5_J1_50") (pintype "passive"))
      (node (ref "U3") (pin "2") (pinfunction "2_2") (pintype "passive"))
    )
    (net (code "41") (name "/ADC3") (class "Default")
      (node (ref "ADC3") (pin "1") (pinfunction "X_1") (pintype "passive"))
      (node (ref "M1") (pin "J1_6") (pinfunction "PH3_J1_6") (pintype "passive"))
      (node (ref "U2") (pin "2") (pinfunction "2_2") (pintype "passive"))
    )
    (net (code "42") (name "/BOOT0") (class "Default")
      (node (ref "M1") (pin "J1_31") (pinfunction "BOOT0_J1_31") (pintype "passive"))
      (node (ref "R18") (pin "2") (pintype "passive"))
      (node (ref "R28") (pin "2") (pintype "passive"))
    )
    (net (code "43") (name "/BOOT1") (class "Default")
      (node (ref "M1") (pin "J1_55") (pinfunction "PB2_J1_55") (pintype "passive"))
      (node (ref "R19") (pin "1") (pintype "passive"))
    )
    (net (code "44") (name "/D+") (class "Default")
      (node (ref "CH340") (pin "5") (pinfunction "UD+_5") (pintype "passive"))
      (node (ref "R6") (pin "2") (pinfunction "2_2") (pintype "passive"))
    )
    (net (code "45") (name "/D-") (class "Default")
      (node (ref "CH340") (pin "6") (pinfunction "UD-_6") (pintype "passive"))
      (node (ref "R5") (pin "2") (pinfunction "2_2") (pintype "passive"))
    )
    (net (code "46") (name "/DAC_OUT1") (class "Default")
      (node (ref "M1") (pin "J1_46") (pinfunction "PA5_J1_46") (pintype "passive"))
      (node (ref "R20") (pin "1") (pintype "passive"))
    )
    (net (code "47") (name "/DAC_OUT2") (class "Default")
      (node (ref "M1") (pin "J1_45") (pinfunction "PA4_J1_45") (pintype "passive"))
      (node (ref "R22") (pin "1") (pintype "passive"))
    )
    (net (code "48") (name "/FMC_A18") (class "Default")
      (node (ref "M1") (pin "J2_14") (pinfunction "PD13_J2_14") (pintype "passive"))
      (node (ref "TFTLCD") (pin "2") (pinfunction "RS_2") (pintype "passive"))
    )
    (net (code "49") (name "/FMC_D0") (class "Default")
      (node (ref "M1") (pin "J2_45") (pinfunction "PD14_J2_45") (pintype "passive"))
      (node (ref "TFTLCD") (pin "6") (pinfunction "D0_6") (pintype "passive"))
    )
    (net (code "50") (name "/FMC_D1") (class "Default")
      (node (ref "M1") (pin "J2_46") (pinfunction "PD15_J2_46") (pintype "passive"))
      (node (ref "TFTLCD") (pin "7") (pinfunction "D1_7") (pintype "passive"))
    )
    (net (code "51") (name "/FMC_D2") (class "Default")
      (node (ref "M1") (pin "J2_47") (pinfunction "PD0_J2_47") (pintype "passive"))
      (node (ref "TFTLCD") (pin "8") (pinfunction "D2_8") (pintype "passive"))
    )
    (net (code "52") (name "/FMC_D3") (class "Default")
      (node (ref "M1") (pin "J2_48") (pinfunction "PD1_J2_48") (pintype "passive"))
      (node (ref "TFTLCD") (pin "9") (pinfunction "D3_9") (pintype "passive"))
    )
    (net (code "53") (name "/FMC_D4") (class "Default")
      (node (ref "M1") (pin "J2_49") (pinfunction "PE7_J2_49") (pintype "passive"))
      (node (ref "TFTLCD") (pin "10") (pinfunction "D4_10") (pintype "passive"))
    )
    (net (code "54") (name "/FMC_D5") (class "Default")
      (node (ref "M1") (pin "J2_50") (pinfunction "PE8_J2_50") (pintype "passive"))
      (node (ref "TFTLCD") (pin "11") (pinfunction "D5_11") (pintype "passive"))
    )
    (net (code "55") (name "/FMC_D6") (class "Default")
      (node (ref "M1") (pin "J2_51") (pinfunction "PE9_J2_51") (pintype "passive"))
      (node (ref "TFTLCD") (pin "12") (pinfunction "D6_12") (pintype "passive"))
    )
    (net (code "56") (name "/FMC_D7") (class "Default")
      (node (ref "M1") (pin "J2_52") (pinfunction "PE10_J2_52") (pintype "passive"))
      (node (ref "TFTLCD") (pin "13") (pinfunction "D7_13") (pintype "passive"))
    )
    (net (code "57") (name "/FMC_D8") (class "Default")
      (node (ref "M1") (pin "J2_53") (pinfunction "PE11_J2_53") (pintype "passive"))
      (node (ref "TFTLCD") (pin "14") (pinfunction "D8_14") (pintype "passive"))
    )
    (net (code "58") (name "/FMC_D9") (class "Default")
      (node (ref "M1") (pin "J2_54") (pinfunction "PE12_J2_54") (pintype "passive"))
      (node (ref "TFTLCD") (pin "15") (pinfunction "D9_15") (pintype "passive"))
    )
    (net (code "59") (name "/FMC_D10") (class "Default")
      (node (ref "M1") (pin "J2_55") (pinfunction "PE13_J2_55") (pintype "passive"))
      (node (ref "TFTLCD") (pin "16") (pinfunction "D10_16") (pintype "passive"))
    )
    (net (code "60") (name "/FMC_D11") (class "Default")
      (node (ref "M1") (pin "J2_56") (pinfunction "PE14_J2_56") (pintype "passive"))
      (node (ref "TFTLCD") (pin "17") (pinfunction "D11_17") (pintype "passive"))
    )
    (net (code "61") (name "/FMC_D12") (class "Default")
      (node (ref "M1") (pin "J2_57") (pinfunction "PE15_J2_57") (pintype "passive"))
      (node (ref "TFTLCD") (pin "18") (pinfunction "D12_18") (pintype "passive"))
    )
    (net (code "62") (name "/FMC_D13") (class "Default")
      (node (ref "M1") (pin "J2_58") (pinfunction "PD8_J2_58") (pintype "passive"))
      (node (ref "TFTLCD") (pin "19") (pinfunction "D13_19") (pintype "passive"))
    )
    (net (code "63") (name "/FMC_D14") (class "Default")
      (node (ref "M1") (pin "J2_59") (pinfunction "PD9_J2_59") (pintype "passive"))
      (node (ref "TFTLCD") (pin "20") (pinfunction "D14_20") (pintype "passive"))
    )
    (net (code "64") (name "/FMC_D15") (class "Default")
      (node (ref "M1") (pin "J2_60") (pinfunction "PD10_J2_60") (pintype "passive"))
      (node (ref "TFTLCD") (pin "21") (pinfunction "D15_21") (pintype "passive"))
    )
    (net (code "65") (name "/FMC_NE1") (class "Default")
      (node (ref "M1") (pin "J1_35") (pinfunction "PD7_J1_35") (pintype "passive"))
      (node (ref "TFTLCD") (pin "1") (pinfunction "LCD_CS_1") (pintype "passive"))
    )
    (net (code "66") (name "/FMC_NOE") (class "Default")
      (node (ref "M1") (pin "J2_26") (pinfunction "PD4_J2_26") (pintype "passive"))
      (node (ref "TFTLCD") (pin "4") (pinfunction "RD_4") (pintype "passive"))
    )
    (net (code "67") (name "/FMC_NWE") (class "Default")
      (node (ref "M1") (pin "J2_22") (pinfunction "PD5_J2_22") (pintype "passive"))
      (node (ref "TFTLCD") (pin "3") (pinfunction "WR/CLK_3") (pintype "passive"))
    )
    (net (code "68") (name "/JTCK") (class "Default")
      (node (ref "M1") (pin "J1_42") (pinfunction "PA14_J1_42") (pintype "passive"))
      (node (ref "R8") (pin "1") (pinfunction "1_1") (pintype "passive"))
      (node (ref "ST-LINK") (pin "5") (pinfunction "5_5") (pintype "passive"))
    )
    (net (code "69") (name "/JTDI") (class "Default")
      (node (ref "M1") (pin "J1_41") (pinfunction "PA15_J1_41") (pintype "passive"))
      (node (ref "R7") (pin "3") (pintype "passive"))
      (node (ref "ST-LINK") (pin "3") (pinfunction "3_3") (pintype "passive"))
    )
    (net (code "70") (name "/JTDO") (class "Default")
      (node (ref "M1") (pin "J1_21") (pinfunction "PB3_J1_21") (pintype "passive"))
      (node (ref "R7") (pin "1") (pintype "passive"))
      (node (ref "ST-LINK") (pin "7") (pinfunction "7_7") (pintype "passive"))
    )
    (net (code "71") (name "/JTMS") (class "Default")
      (node (ref "M1") (pin "J1_43") (pinfunction "PA13_J1_43") (pintype "passive"))
      (node (ref "R7") (pin "2") (pintype "passive"))
      (node (ref "ST-LINK") (pin "4") (pinfunction "4_4") (pintype "passive"))
    )
    (net (code "72") (name "/JTRST") (class "Default")
      (node (ref "M1") (pin "J1_22") (pinfunction "PB4_J1_22") (pintype "passive"))
      (node (ref "R7") (pin "4") (pintype "passive"))
      (node (ref "ST-LINK") (pin "2") (pinfunction "2_2") (pintype "passive"))
    )
    (net (code "73") (name "/KEY0") (class "Default")
      (node (ref "C37") (pin "1") (pintype "passive"))
      (node (ref "KEY1") (pin "1") (pinfunction "1_1") (pintype "passive"))
      (node (ref "M1") (pin "J2_44") (pinfunction "PE1_J2_44") (pintype "passive"))
      (node (ref "R17") (pin "4") (pintype "passive"))
    )
    (net (code "74") (name "/KEY1") (class "Default")
      (node (ref "C38") (pin "1") (pintype "passive"))
      (node (ref "KEY2") (pin "1") (pinfunction "1_1") (pintype "passive"))
      (node (ref "M1") (pin "J2_43") (pinfunction "PE0_J2_43") (pintype "passive"))
      (node (ref "R17") (pin "3") (pintype "passive"))
    )
    (net (code "75") (name "/KEY2") (class "Default")
      (node (ref "C39") (pin "1") (pintype "passive"))
      (node (ref "KEY3") (pin "1") (pinfunction "1_1") (pintype "passive"))
      (node (ref "M1") (pin "J2_37") (pinfunction "PI5_J2_37") (pintype "passive"))
      (node (ref "R17") (pin "2") (pintype "passive"))
    )
    (net (code "76") (name "/KEY3") (class "Default")
      (node (ref "C40") (pin "1") (pintype "passive"))
      (node (ref "KEY4") (pin "1") (pinfunction "1_1") (pintype "passive"))
      (node (ref "M1") (pin "J2_36") (pinfunction "PI4_J2_36") (pintype "passive"))
      (node (ref "R17") (pin "1") (pintype "passive"))
    )
    (net (code "77") (name "/LCD_BL") (class "Default")
      (node (ref "M1") (pin "J1_23") (pinfunction "PB5_J1_23") (pintype "passive"))
      (node (ref "R25") (pin "2") (pintype "passive"))
      (node (ref "TFTLCD") (pin "23") (pinfunction "BL_23") (pintype "passive"))
    )
    (net (code "78") (name "/LED0") (class "Default")
      (node (ref "LD3") (pin "2") (pinfunction "K_2") (pintype "passive"))
      (node (ref "M1") (pin "J1_56") (pinfunction "PB0_J1_56") (pintype "passive"))
    )
    (net (code "79") (name "/LED1") (class "Default")
      (node (ref "LD4") (pin "2") (pinfunction "K_2") (pintype "passive"))
      (node (ref "M1") (pin "J1_57") (pinfunction "PB1_J1_57") (pintype "passive"))
    )
    (net (code "80") (name "/PA8") (class "Default")
      (node (ref "IO1") (pin "12") (pinfunction "12_12") (pintype "passive"))
      (node (ref "M1") (pin "J2_20") (pinfunction "PA8_J2_20") (pintype "passive"))
    )
    (net (code "81") (name "/PA9") (class "Default")
      (node (ref "M1") (pin "J1_51") (pinfunction "PA9_J1_51") (pintype "passive"))
      (node (ref "P1") (pin "3") (pinfunction "3_3") (pintype "passive"))
    )
    (net (code "82") (name "/PA10") (class "Default")
      (node (ref "M1") (pin "J1_52") (pinfunction "PA10_J1_52") (pintype "passive"))
      (node (ref "P1") (pin "1") (pinfunction "1_1") (pintype "passive"))
    )
    (net (code "83") (name "/PB10") (class "Default")
      (node (ref "M1") (pin "J2_2") (pinfunction "PB10_J2_2") (pintype "passive"))
      (node (ref "串口屏") (pin "3") (pinfunction "3_3") (pintype "passive"))
    )
    (net (code "84") (name "/PB11") (class "Default")
      (node (ref "M1") (pin "J2_1") (pinfunction "PB11_J2_1") (pintype "passive"))
      (node (ref "串口屏") (pin "2") (pinfunction "2_2") (pintype "passive"))
    )
    (net (code "85") (name "/PB12") (class "Default")
      (node (ref "IO1") (pin "2") (pinfunction "2_2") (pintype "passive"))
      (node (ref "M1") (pin "J2_4") (pinfunction "PB12_J2_4") (pintype "passive"))
    )
    (net (code "86") (name "/PB13") (class "Default")
      (node (ref "IO1") (pin "3") (pinfunction "3_3") (pintype "passive"))
      (node (ref "M1") (pin "J2_5") (pinfunction "PB13_J2_5") (pintype "passive"))
    )
    (net (code "87") (name "/PB14") (class "Default")
      (node (ref "IO1") (pin "4") (pinfunction "4_4") (pintype "passive"))
      (node (ref "M1") (pin "J2_6") (pinfunction "PB14_J2_6") (pintype "passive"))
    )
    (net (code "88") (name "/PB15") (class "Default")
      (node (ref "IO1") (pin "5") (pinfunction "5_5") (pintype "passive"))
      (node (ref "M1") (pin "J2_7") (pinfunction "PB15_J2_7") (pintype "passive"))
    )
    (net (code "89") (name "/PC6") (class "Default")
      (node (ref "IO1") (pin "10") (pinfunction "10_10") (pintype "passive"))
      (node (ref "M1") (pin "J2_16") (pinfunction "PC6_J2_16") (pintype "passive"))
    )
    (net (code "90") (name "/PC7") (class "Default")
      (node (ref "IO1") (pin "11") (pinfunction "11_11") (pintype "passive"))
      (node (ref "M1") (pin "J2_17") (pinfunction "PC7_J2_17") (pintype "passive"))
    )
    (net (code "91") (name "/PC8") (class "Default")
      (node (ref "J2") (pin "7") (pinfunction "DATA0_7") (pintype "passive"))
      (node (ref "M1") (pin "J2_18") (pinfunction "PC8_J2_18") (pintype "passive"))
      (node (ref "R9") (pin "7") (pintype "passive"))
    )
    (net (code "92") (name "/PC9") (class "Default")
      (node (ref "J2") (pin "8") (pinfunction "DATA1_8") (pintype "passive"))
      (node (ref "M1") (pin "J2_19") (pinfunction "PC9_J2_19") (pintype "passive"))
      (node (ref "R9") (pin "6") (pintype "passive"))
    )
    (net (code "93") (name "/PC10") (class "Default")
      (node (ref "J2") (pin "1") (pinfunction "DATA2_1") (pintype "passive"))
      (node (ref "M1") (pin "J1_40") (pinfunction "PC10_J1_40") (pintype "passive"))
      (node (ref "R9") (pin "5") (pintype "passive"))
    )
    (net (code "94") (name "/PC11") (class "Default")
      (node (ref "J2") (pin "2") (pinfunction "CD/DATA3_2") (pintype "passive"))
      (node (ref "M1") (pin "J1_39") (pinfunction "PC11_J1_39") (pintype "passive"))
      (node (ref "R10") (pin "2") (pinfunction "2_2") (pintype "passive"))
    )
    (net (code "95") (name "/PC12") (class "Default")
      (node (ref "J2") (pin "5") (pinfunction "CLK_5") (pintype "passive"))
      (node (ref "M1") (pin "J1_38") (pinfunction "PC12_J1_38") (pintype "passive"))
    )
    (net (code "96") (name "/PD2") (class "Default")
      (node (ref "J2") (pin "3") (pinfunction "CMD_3") (pintype "passive"))
      (node (ref "M1") (pin "J1_37") (pinfunction "PD2_J1_37") (pintype "passive"))
      (node (ref "R9") (pin "8") (pintype "passive"))
    )
    (net (code "97") (name "/PD6") (class "Default")
      (node (ref "IO1") (pin "17") (pinfunction "17_17") (pintype "passive"))
      (node (ref "M1") (pin "J2_27") (pinfunction "PD6_J2_27") (pintype "passive"))
    )
    (net (code "98") (name "/PD11") (class "Default")
      (node (ref "IO1") (pin "14") (pinfunction "14_14") (pintype "passive"))
      (node (ref "M1") (pin "J2_23") (pinfunction "PD11_J2_23") (pintype "passive"))
    )
    (net (code "99") (name "/PD12") (class "Default")
      (node (ref "IO1") (pin "13") (pinfunction "13_13") (pintype "passive"))
      (node (ref "M1") (pin "J2_21") (pinfunction "PD12_J2_21") (pintype "passive"))
    )
    (net (code "100") (name "/PG3") (class "Default")
      (node (ref "M1") (pin "J2_13") (pinfunction "PG3_J2_13") (pintype "passive"))
      (node (ref "TFTLCD") (pin "29") (pinfunction "MISO_29") (pintype "passive"))
    )
    (net (code "101") (name "/PG6") (class "Default")
      (node (ref "IO1") (pin "9") (pinfunction "9_9") (pintype "passive"))
      (node (ref "M1") (pin "J2_15") (pinfunction "PG6_J2_15") (pintype "passive"))
    )
    (net (code "102") (name "/PG12") (class "Default")
      (node (ref "IO1") (pin "16") (pinfunction "16_16") (pintype "passive"))
      (node (ref "M1") (pin "J2_25") (pinfunction "PG12_J2_25") (pintype "passive"))
    )
    (net (code "103") (name "/PH6") (class "Default")
      (node (ref "M1") (pin "J2_8") (pinfunction "PH6_J2_8") (pintype "passive"))
      (node (ref "TFTLCD") (pin "34") (pinfunction "CLK_34") (pintype "passive"))
    )
    (net (code "104") (name "/PH7") (class "Default")
      (node (ref "M1") (pin "J2_9") (pinfunction "PH7_J2_9") (pintype "passive"))
      (node (ref "TFTLCD") (pin "31") (pinfunction "T_PEN_31") (pintype "passive"))
    )
    (net (code "105") (name "/PH8") (class "Default")
      (node (ref "IO1") (pin "1") (pinfunction "1_1") (pintype "passive"))
      (node (ref "M1") (pin "J2_3") (pinfunction "PH8_J2_3") (pintype "passive"))
    )
    (net (code "106") (name "/PH9") (class "Default")
      (node (ref "IO1") (pin "6") (pinfunction "6_6") (pintype "passive"))
      (node (ref "M1") (pin "J2_10") (pinfunction "PH9_J2_10") (pintype "passive"))
    )
    (net (code "107") (name "/PH10") (class "Default")
      (node (ref "IO1") (pin "7") (pinfunction "7_7") (pintype "passive"))
      (node (ref "M1") (pin "J2_11") (pinfunction "PH10_J2_11") (pintype "passive"))
    )
    (net (code "108") (name "/PH11") (class "Default")
      (node (ref "IO1") (pin "8") (pinfunction "8_8") (pintype "passive"))
      (node (ref "M1") (pin "J2_12") (pinfunction "PH11_J2_12") (pintype "passive"))
    )
    (net (code "109") (name "/PH12") (class "Default")
      (node (ref "IO1") (pin "15") (pinfunction "15_15") (pintype "passive"))
      (node (ref "M1") (pin "J2_24") (pinfunction "PH12_J2_24") (pintype "passive"))
    )
    (net (code "110") (name "/PH13") (class "Default")
      (node (ref "IO1") (pin "20") (pinfunction "20_20") (pintype "passive"))
      (node (ref "M1") (pin "J2_30") (pinfunction "PH13_J2_30") (pintype "passive"))
    )
    (net (code "111") (name "/PH14") (class "Default")
      (node (ref "IO1") (pin "19") (pinfunction "19_19") (pintype "passive"))
      (node (ref "M1") (pin "J2_29") (pinfunction "PH14_J2_29") (pintype "passive"))
    )
    (net (code "112") (name "/PH15") (class "Default")
      (node (ref "IO1") (pin "18") (pinfunction "18_18") (pintype "passive"))
      (node (ref "M1") (pin "J2_28") (pinfunction "PH15_J2_28") (pintype "passive"))
    )
    (net (code "113") (name "/PI3") (class "Default")
      (node (ref "M1") (pin "J2_41") (pinfunction "PI3_J2_41") (pintype "passive"))
      (node (ref "TFTLCD") (pin "30") (pinfunction "MOSI_30") (pintype "passive"))
    )
    (net (code "114") (name "/PI8") (class "Default")
      (node (ref "M1") (pin "J2_40") (pinfunction "PI8_J2_40") (pintype "passive"))
      (node (ref "TFTLCD") (pin "33") (pinfunction "T_CS_33") (pintype "passive"))
    )
    (net (code "115") (name "/RESET") (class "Default")
      (node (ref "1N4148") (pin "1") (pinfunction "A_1") (pintype "passive"))
      (node (ref "C3") (pin "2") (pintype "passive"))
      (node (ref "M1") (pin "J1_10") (pinfunction "RESET_J1_10") (pintype "passive"))
      (node (ref "R1") (pin "1") (pintype "passive"))
      (node (ref "RESET") (pin "1") (pinfunction "1_1") (pintype "passive"))
      (node (ref "ST-LINK") (pin "8") (pinfunction "8_8") (pintype "passive"))
      (node (ref "TFTLCD") (pin "5") (pinfunction "RST_5") (pintype "passive"))
    )
    (net (code "116") (name "/RX") (class "Default")
      (node (ref "P1") (pin "2") (pinfunction "2_2") (pintype "passive"))
      (node (ref "R3") (pin "2") (pinfunction "2_2") (pintype "passive"))
    )
    (net (code "117") (name "/TX") (class "Default")
      (node (ref "P1") (pin "4") (pinfunction "4_4") (pintype "passive"))
      (node (ref "R2") (pin "2") (pinfunction "2_2") (pintype "passive"))
    )
    (net (code "118") (name "/VREF+") (class "Default")
      (node (ref "M1") (pin "J1_2") (pinfunction "VREF+_J1_2") (pintype "passive"))
      (node (ref "VREF") (pin "1") (pinfunction "1_1") (pintype "passive"))
    )
    (net (code "119") (name "GND") (class "Default")
      (node (ref "3V3-GND") (pin "1") (pinfunction "1_1") (pintype "passive"))
      (node (ref "3V3-GND") (pin "11") (pinfunction "11_11") (pintype "passive"))
      (node (ref "3V3-GND") (pin "13") (pinfunction "13_13") (pintype "passive"))
      (node (ref "3V3-GND") (pin "15") (pinfunction "15_15") (pintype "passive"))
      (node (ref "3V3-GND") (pin "3") (pinfunction "3_3") (pintype "passive"))
      (node (ref "3V3-GND") (pin "5") (pinfunction "5_5") (pintype "passive"))
      (node (ref "3V3-GND") (pin "7") (pinfunction "7_7") (pintype "passive"))
      (node (ref "3V3-GND") (pin "9") (pinfunction "9_9") (pintype "passive"))
      (node (ref "5V-GND") (pin "1") (pinfunction "1_1") (pintype "passive"))
      (node (ref "5V-GND") (pin "11") (pinfunction "11_11") (pintype "passive"))
      (node (ref "5V-GND") (pin "13") (pinfunction "13_13") (pintype "passive"))
      (node (ref "5V-GND") (pin "15") (pinfunction "15_15") (pintype "passive"))
      (node (ref "5V-GND") (pin "3") (pinfunction "3_3") (pintype "passive"))
      (node (ref "5V-GND") (pin "5") (pinfunction "5_5") (pintype "passive"))
      (node (ref "5V-GND") (pin "7") (pinfunction "7_7") (pintype "passive"))
      (node (ref "5V-GND") (pin "9") (pinfunction "9_9") (pintype "passive"))
      (node (ref "9V") (pin "2") (pintype "passive"))
      (node (ref "9V") (pin "3") (pintype "passive"))
      (node (ref "9V1") (pin "2") (pinfunction "2_2") (pintype "passive"))
      (node (ref "9V2") (pin "1") (pinfunction "1_1") (pintype "passive"))
      (node (ref "AD9959") (pin "2") (pinfunction "2_2") (pintype "passive"))
      (node (ref "ADC1") (pin "2") (pinfunction "Y_2") (pintype "passive"))
      (node (ref "ADC2") (pin "2") (pinfunction "Y_2") (pintype "passive"))
      (node (ref "ADC3") (pin "2") (pinfunction "Y_2") (pintype "passive"))
      (node (ref "ADF4351") (pin "3") (pinfunction "3_3") (pintype "passive"))
      (node (ref "ADF4351-1") (pin "3") (pinfunction "3_3") (pintype "passive"))
      (node (ref "ADS1256") (pin "1") (pinfunction "1_1") (pintype "passive"))
      (node (ref "ADS1256") (pin "10") (pinfunction "10_10") (pintype "passive"))
      (node (ref "BOOT") (pin "5") (pinfunction "5_5") (pintype "passive"))
      (node (ref "BOOT") (pin "6") (pinfunction "6_6") (pintype "passive"))
      (node (ref "C1") (pin "2") (pinfunction "2_2") (pintype "passive"))
      (node (ref "C10") (pin "1") (pintype "passive"))
      (node (ref "C11") (pin "1") (pintype "passive"))
      (node (ref "C12") (pin "1") (pintype "passive"))
      (node (ref "C13") (pin "1") (pintype "passive"))
      (node (ref "C14") (pin "1") (pintype "passive"))
      (node (ref "C15") (pin "1") (pintype "passive"))
      (node (ref "C16") (pin "1") (pintype "passive"))
      (node (ref "C17") (pin "1") (pintype "passive"))
      (node (ref "C18") (pin "1") (pintype "passive"))
      (node (ref "C19") (pin "1") (pintype "passive"))
      (node (ref "C2") (pin "1") (pinfunction "1_1") (pintype "passive"))
      (node (ref "C20") (pin "1") (pintype "passive"))
      (node (ref "C21") (pin "1") (pintype "passive"))
      (node (ref "C22") (pin "1") (pintype "passive"))
      (node (ref "C23") (pin "1") (pintype "passive"))
      (node (ref "C24") (pin "1") (pintype "passive"))
      (node (ref "C25") (pin "1") (pintype "passive"))
      (node (ref "C26") (pin "1") (pintype "passive"))
      (node (ref "C27") (pin "1") (pintype "passive"))
      (node (ref "C28") (pin "1") (pintype "passive"))
      (node (ref "C29") (pin "1") (pintype "passive"))
      (node (ref "C3") (pin "1") (pintype "passive"))
      (node (ref "C30") (pin "1") (pintype "passive"))
      (node (ref "C31") (pin "1") (pintype "passive"))
      (node (ref "C32") (pin "1") (pintype "passive"))
      (node (ref "C33") (pin "1") (pintype "passive"))
      (node (ref "C34") (pin "1") (pintype "passive"))
      (node (ref "C35") (pin "1") (pintype "passive"))
      (node (ref "C36") (pin "1") (pinfunction "1_1") (pintype "passive"))
      (node (ref "C37") (pin "2") (pintype "passive"))
      (node (ref "C38") (pin "2") (pintype "passive"))
      (node (ref "C39") (pin "2") (pintype "passive"))
      (node (ref "C4") (pin "1") (pinfunction "1_1") (pintype "passive"))
      (node (ref "C40") (pin "2") (pintype "passive"))
      (node (ref "C41") (pin "1") (pinfunction "1_1") (pintype "passive"))
      (node (ref "C42") (pin "1") (pintype "passive"))
      (node (ref "C43") (pin "1") (pintype "passive"))
      (node (ref "C44") (pin "1") (pintype "passive"))
      (node (ref "C45") (pin "1") (pintype "passive"))
      (node (ref "C46") (pin "1") (pintype "passive"))
      (node (ref "C5") (pin "1") (pinfunction "1_1") (pintype "passive"))
      (node (ref "C6") (pin "1") (pinfunction "1_1") (pintype "passive"))
      (node (ref "C7") (pin "2") (pinfunction "2_2") (pintype "passive"))
      (node (ref "C8") (pin "1") (pintype "passive"))
      (node (ref "C9") (pin "1") (pintype "passive"))
      (node (ref "CH340") (pin "1") (pinfunction "GND_1") (pintype "passive"))
      (node (ref "DAC1") (pin "2") (pinfunction "Y_2") (pintype "passive"))
      (node (ref "DAC2") (pin "2") (pinfunction "Y_2") (pintype "passive"))
      (node (ref "J2") (pin "10") (pinfunction "GND_10") (pintype "passive"))
      (node (ref "J2") (pin "6") (pinfunction "VSS_6") (pintype "passive"))
      (node (ref "KEY1") (pin "2") (pinfunction "2_2") (pintype "passive"))
      (node (ref "KEY2") (pin "2") (pinfunction "2_2") (pintype "passive"))
      (node (ref "KEY3") (pin "2") (pinfunction "2_2") (pintype "passive"))
      (node (ref "KEY4") (pin "2") (pinfunction "2_2") (pintype "passive"))
      (node (ref "LD1") (pin "2") (pinfunction "K_2") (pintype "passive"))
      (node (ref "LD2") (pin "2") (pinfunction "K_2") (pintype "passive"))
      (node (ref "LMX2571") (pin "2") (pinfunction "2_2") (pintype "passive"))
      (node (ref "M1") (pin "J1_1") (pinfunction "GND_J1_1") (pintype "passive"))
      (node (ref "M1") (pin "J1_30") (pinfunction "GND_J1_30") (pintype "passive"))
      (node (ref "M1") (pin "J2_31") (pinfunction "GND_J2_31") (pintype "passive"))
      (node (ref "Mini-USB") (pin "4") (pinfunction "NC_4") (pintype "passive"))
      (node (ref "Mini-USB") (pin "5") (pinfunction "GND_5") (pintype "passive"))
      (node (ref "R25") (pin "1") (pintype "passive"))
      (node (ref "R8") (pin "2") (pinfunction "2_2") (pintype "passive"))
      (node (ref "RESET") (pin "2") (pinfunction "2_2") (pintype "passive"))
      (node (ref "ST-LINK") (pin "11") (pinfunction "11_11") (pintype "passive"))
      (node (ref "ST-LINK") (pin "12") (pinfunction "12_12") (pintype "passive"))
      (node (ref "ST-LINK") (pin "13") (pinfunction "13_13") (pintype "passive"))
      (node (ref "ST-LINK") (pin "14") (pinfunction "14_14") (pintype "passive"))
      (node (ref "ST-LINK") (pin "15") (pinfunction "15_15") (pintype "passive"))
      (node (ref "ST-LINK") (pin "16") (pinfunction "16_16") (pintype "passive"))
      (node (ref "ST-LINK") (pin "17") (pinfunction "17_17") (pintype "passive"))
      (node (ref "ST-LINK") (pin "18") (pinfunction "18_18") (pintype "passive"))
      (node (ref "ST-LINK") (pin "19") (pinfunction "19_19") (pintype "passive"))
      (node (ref "TFTLCD") (pin "22") (pinfunction "GND_22") (pintype "passive"))
      (node (ref "TFTLCD") (pin "26") (pinfunction "GND_26") (pintype "passive"))
      (node (ref "TFTLCD") (pin "27") (pinfunction "GND_27") (pintype "passive"))
      (node (ref "TPS-3V3") (pin "11") (pinfunction "0P2V_11") (pintype "passive"))
      (node (ref "TPS-3V3") (pin "12") (pinfunction "0P1V_12") (pintype "passive"))
      (node (ref "TPS-3V3") (pin "21") (pinfunction "PAD_21") (pintype "passive"))
      (node (ref "TPS-3V3") (pin "7") (pinfunction "GND_7") (pintype "power_in"))
      (node (ref "TPS-3V3") (pin "8") (pinfunction "1P6V_8") (pintype "passive"))
      (node (ref "TPS-5V") (pin "10") (pinfunction "0P4V_10") (pintype "passive"))
      (node (ref "TPS-5V") (pin "21") (pinfunction "PAD_21") (pintype "passive"))
      (node (ref "TPS-5V") (pin "6") (pinfunction "3P2V_6") (pintype "passive"))
      (node (ref "TPS-5V") (pin "7") (pinfunction "GND_7") (pintype "power_in"))
      (node (ref "U2") (pin "1") (pinfunction "1_1") (pintype "passive"))
      (node (ref "U3") (pin "1") (pinfunction "1_1") (pintype "passive"))
      (node (ref "U4") (pin "1") (pinfunction "1_1") (pintype "passive"))
      (node (ref "串口屏") (pin "1") (pinfunction "1_1") (pintype "passive"))
    )
    (net (code "120") (name "Net-(1N4148-K)") (class "Default")
      (node (ref "1N4148") (pin "2") (pinfunction "K_2") (pintype "passive"))
      (node (ref "R30") (pin "1") (pintype "passive"))
      (node (ref "S8050") (pin "3") (pinfunction "C_3") (pintype "passive"))
    )
    (net (code "121") (name "Net-(BOOT-Pad3)") (class "Default")
      (node (ref "BOOT") (pin "3") (pinfunction "3_3") (pintype "passive"))
      (node (ref "R18") (pin "1") (pintype "passive"))
    )
    (net (code "122") (name "Net-(BOOT-Pad4)") (class "Default")
      (node (ref "BOOT") (pin "4") (pinfunction "4_4") (pintype "passive"))
      (node (ref "R19") (pin "2") (pintype "passive"))
    )
    (net (code "123") (name "Net-(C42-Pad2)") (class "Default")
      (node (ref "C42") (pin "2") (pintype "passive"))
      (node (ref "R20") (pin "2") (pintype "passive"))
      (node (ref "R21") (pin "1") (pintype "passive"))
    )
    (net (code "124") (name "Net-(C44-Pad2)") (class "Default")
      (node (ref "C44") (pin "2") (pintype "passive"))
      (node (ref "R22") (pin "2") (pintype "passive"))
      (node (ref "R23") (pin "1") (pintype "passive"))
    )
    (net (code "125") (name "Net-(C46-Pad2)") (class "Default")
      (node (ref "C46") (pin "2") (pintype "passive"))
      (node (ref "R24") (pin "1") (pintype "passive"))
      (node (ref "VREF") (pin "2") (pinfunction "2_2") (pintype "passive"))
    )
    (net (code "126") (name "Net-(CH340-DTR)") (class "Default")
      (node (ref "CH340") (pin "13") (pinfunction "DTR_13") (pintype "passive"))
      (node (ref "R29") (pin "1") (pintype "passive"))
    )
    (net (code "127") (name "Net-(CH340-DTS)") (class "Default")
      (node (ref "CH340") (pin "14") (pinfunction "DTS_14") (pintype "passive"))
      (node (ref "R27") (pin "2") (pintype "passive"))
      (node (ref "S8050") (pin "2") (pinfunction "E_2") (pintype "passive"))
    )
    (net (code "128") (name "Net-(CH340-RXD)") (class "Default")
      (node (ref "CH340") (pin "3") (pinfunction "RXD_3") (pintype "passive"))
      (node (ref "R3") (pin "1") (pinfunction "1_1") (pintype "passive"))
    )
    (net (code "129") (name "Net-(CH340-TXD)") (class "Default")
      (node (ref "CH340") (pin "2") (pinfunction "TXD_2") (pintype "passive"))
      (node (ref "R2") (pin "1") (pinfunction "1_1") (pintype "passive"))
    )
    (net (code "130") (name "Net-(CH340-V3)") (class "Default")
      (node (ref "C4") (pin "2") (pinfunction "2_2") (pintype "passive"))
      (node (ref "CH340") (pin "4") (pinfunction "V3_4") (pintype "passive"))
    )
    (net (code "131") (name "Net-(CH340-VCC)") (class "Default")
      (node (ref "C7") (pin "1") (pinfunction "1_1") (pintype "passive"))
      (node (ref "CH340") (pin "16") (pinfunction "VCC_16") (pintype "passive"))
      (node (ref "R4") (pin "2") (pinfunction "2_2") (pintype "passive"))
    )
    (net (code "132") (name "Net-(CH340-XI)") (class "Default")
      (node (ref "C5") (pin "2") (pinfunction "2_2") (pintype "passive"))
      (node (ref "CH340") (pin "7") (pinfunction "XI_7") (pintype "passive"))
      (node (ref "Y1") (pin "2") (pinfunction "OSC2_2") (pintype "passive"))
    )
    (net (code "133") (name "Net-(CH340-XO)") (class "Default")
      (node (ref "C6") (pin "2") (pinfunction "2_2") (pintype "passive"))
      (node (ref "CH340") (pin "8") (pinfunction "XO_8") (pintype "passive"))
      (node (ref "Y1") (pin "1") (pinfunction "OSC1_1") (pintype "passive"))
    )
    (net (code "134") (name "Net-(DAC1-X)") (class "Default")
      (node (ref "C43") (pin "2") (pintype "passive"))
      (node (ref "DAC1") (pin "1") (pinfunction "X_1") (pintype "passive"))
      (node (ref "R21") (pin "2") (pintype "passive"))
    )
    (net (code "135") (name "Net-(DAC2-X)") (class "Default")
      (node (ref "C45") (pin "2") (pintype "passive"))
      (node (ref "DAC2") (pin "1") (pinfunction "X_1") (pintype "passive"))
      (node (ref "R23") (pin "2") (pintype "passive"))
    )
    (net (code "136") (name "Net-(LD1-A)") (class "Default")
      (node (ref "LD1") (pin "1") (pinfunction "A_1") (pintype "passive"))
      (node (ref "R11") (pin "2") (pintype "passive"))
    )
    (net (code "137") (name "Net-(LD2-A)") (class "Default")
      (node (ref "LD2") (pin "1") (pinfunction "A_1") (pintype "passive"))
      (node (ref "R12") (pin "2") (pintype "passive"))
    )
    (net (code "138") (name "Net-(LD3-A)") (class "Default")
      (node (ref "LD3") (pin "1") (pinfunction "A_1") (pintype "passive"))
      (node (ref "R15") (pin "1") (pintype "passive"))
    )
    (net (code "139") (name "Net-(LD4-A)") (class "Default")
      (node (ref "LD4") (pin "1") (pinfunction "A_1") (pintype "passive"))
      (node (ref "R16") (pin "1") (pintype "passive"))
    )
    (net (code "140") (name "Net-(Mini-USB-D+)") (class "Default")
      (node (ref "Mini-USB") (pin "3") (pinfunction "D+_3") (pintype "passive"))
      (node (ref "R6") (pin "1") (pinfunction "1_1") (pintype "passive"))
    )
    (net (code "141") (name "Net-(Mini-USB-D-)") (class "Default")
      (node (ref "Mini-USB") (pin "2") (pinfunction "D-_2") (pintype "passive"))
      (node (ref "R5") (pin "1") (pinfunction "1_1") (pintype "passive"))
    )
    (net (code "142") (name "Net-(S8050-B)") (class "Default")
      (node (ref "R29") (pin "2") (pintype "passive"))
      (node (ref "S8050") (pin "1") (pinfunction "B_1") (pintype "passive"))
    )
    (net (code "143") (name "Net-(S8550-B)") (class "Default")
      (node (ref "R27") (pin "1") (pintype "passive"))
      (node (ref "S8550") (pin "1") (pinfunction "B_1") (pintype "passive"))
    )
    (net (code "144") (name "Net-(S8550-C)") (class "Default")
      (node (ref "R28") (pin "1") (pintype "passive"))
      (node (ref "S8550") (pin "3") (pinfunction "C_3") (pintype "passive"))
    )
    (net (code "145") (name "Net-(TPS-3V3-NR)") (class "Default")
      (node (ref "C20") (pin "2") (pintype "passive"))
      (node (ref "TPS-3V3") (pin "14") (pinfunction "NR_14") (pintype "input"))
    )
    (net (code "146") (name "Net-(TPS-5V-NR)") (class "Default")
      (node (ref "C10") (pin "2") (pintype "passive"))
      (node (ref "TPS-5V") (pin "14") (pinfunction "NR_14") (pintype "input"))
    )
    (net (code "147") (name "VCC") (class "Default")
      (node (ref "9V") (pin "1") (pintype "passive"))
      (node (ref "9V1") (pin "1") (pinfunction "1_1") (pintype "passive"))
      (node (ref "9V2") (pin "2") (pinfunction "2_2") (pintype "passive"))
      (node (ref "SUPPLY") (pin "3") (pinfunction "NO1_3") (pintype "passive"))
      (node (ref "SUPPLY") (pin "6") (pinfunction "NC2_6") (pintype "passive"))
    )
    (net (code "148") (name "VCC-3.3") (class "Default")
      (node (ref "3V3-GND") (pin "10") (pinfunction "10_10") (pintype "passive"))
      (node (ref "3V3-GND") (pin "12") (pinfunction "12_12") (pintype "passive"))
      (node (ref "3V3-GND") (pin "14") (pinfunction "14_14") (pintype "passive"))
      (node (ref "3V3-GND") (pin "16") (pinfunction "16_16") (pintype "passive"))
      (node (ref "3V3-GND") (pin "2") (pinfunction "2_2") (pintype "passive"))
      (node (ref "3V3-GND") (pin "4") (pinfunction "4_4") (pintype "passive"))
      (node (ref "3V3-GND") (pin "6") (pinfunction "6_6") (pintype "passive"))
      (node (ref "3V3-GND") (pin "8") (pinfunction "8_8") (pintype "passive"))
      (node (ref "BOOT") (pin "1") (pinfunction "1_1") (pintype "passive"))
      (node (ref "BOOT") (pin "2") (pinfunction "2_2") (pintype "passive"))
      (node (ref "C1") (pin "1") (pinfunction "1_1") (pintype "passive"))
      (node (ref "C21") (pin "2") (pintype "passive"))
      (node (ref "C22") (pin "2") (pintype "passive"))
      (node (ref "C23") (pin "2") (pintype "passive"))
      (node (ref "C24") (pin "2") (pintype "passive"))
      (node (ref "C25") (pin "2") (pintype "passive"))
      (node (ref "C26") (pin "2") (pintype "passive"))
      (node (ref "C27") (pin "2") (pintype "passive"))
      (node (ref "J2") (pin "4") (pinfunction "VDD_4") (pintype "passive"))
      (node (ref "R1") (pin "2") (pintype "passive"))
      (node (ref "R10") (pin "1") (pinfunction "1_1") (pintype "passive"))
      (node (ref "R12") (pin "1") (pintype "passive"))
      (node (ref "R15") (pin "2") (pintype "passive"))
      (node (ref "R16") (pin "2") (pintype "passive"))
      (node (ref "R17") (pin "5") (pintype "passive"))
      (node (ref "R17") (pin "6") (pintype "passive"))
      (node (ref "R17") (pin "7") (pintype "passive"))
      (node (ref "R17") (pin "8") (pintype "passive"))
      (node (ref "R24") (pin "2") (pintype "passive"))
      (node (ref "R30") (pin "2") (pintype "passive"))
      (node (ref "R7") (pin "5") (pintype "passive"))
      (node (ref "R7") (pin "6") (pintype "passive"))
      (node (ref "R7") (pin "7") (pintype "passive"))
      (node (ref "R7") (pin "8") (pintype "passive"))
      (node (ref "R9") (pin "1") (pintype "passive"))
      (node (ref "R9") (pin "2") (pintype "passive"))
      (node (ref "R9") (pin "3") (pintype "passive"))
      (node (ref "R9") (pin "4") (pintype "passive"))
      (node (ref "S8550") (pin "2") (pinfunction "E_2") (pintype "passive"))
      (node (ref "ST-LINK") (pin "1") (pinfunction "1_1") (pintype "passive"))
      (node (ref "ST-LINK") (pin "20") (pinfunction "20_20") (pintype "passive"))
      (node (ref "TFTLCD") (pin "24") (pinfunction "VDD3.3_24") (pintype "passive"))
      (node (ref "TFTLCD") (pin "25") (pinfunction "VDD3.3_25") (pintype "passive"))
      (node (ref "TPS-3V3") (pin "1") (pinfunction "OUT_1") (pintype "power_in"))
      (node (ref "TPS-3V3") (pin "20") (pinfunction "OUT_20") (pintype "power_in"))
      (node (ref "TPS-3V3") (pin "3") (pinfunction "SENSE_FB_3") (pintype "input"))
      (node (ref "U2") (pin "3") (pinfunction "3_3") (pintype "passive"))
      (node (ref "U3") (pin "3") (pinfunction "3_3") (pintype "passive"))
      (node (ref "U4") (pin "3") (pinfunction "3_3") (pintype "passive"))
    )
    (net (code "149") (name "VCC-5") (class "Default")
      (node (ref "5V-GND") (pin "10") (pinfunction "10_10") (pintype "passive"))
      (node (ref "5V-GND") (pin "12") (pinfunction "12_12") (pintype "passive"))
      (node (ref "5V-GND") (pin "14") (pinfunction "14_14") (pintype "passive"))
      (node (ref "5V-GND") (pin "16") (pinfunction "16_16") (pintype "passive"))
      (node (ref "5V-GND") (pin "2") (pinfunction "2_2") (pintype "passive"))
      (node (ref "5V-GND") (pin "4") (pinfunction "4_4") (pintype "passive"))
      (node (ref "5V-GND") (pin "6") (pinfunction "6_6") (pintype "passive"))
      (node (ref "5V-GND") (pin "8") (pinfunction "8_8") (pintype "passive"))
      (node (ref "C11") (pin "2") (pintype "passive"))
      (node (ref "C12") (pin "2") (pintype "passive"))
      (node (ref "C13") (pin "2") (pintype "passive"))
      (node (ref "C14") (pin "2") (pintype "passive"))
      (node (ref "C15") (pin "2") (pintype "passive"))
      (node (ref "C16") (pin "2") (pintype "passive"))
      (node (ref "C17") (pin "2") (pintype "passive"))
      (node (ref "C18") (pin "2") (pintype "passive"))
      (node (ref "C19") (pin "2") (pintype "passive"))
      (node (ref "C2") (pin "2") (pinfunction "2_2") (pintype "passive"))
      (node (ref "C28") (pin "2") (pintype "passive"))
      (node (ref "C29") (pin "2") (pintype "passive"))
      (node (ref "C30") (pin "2") (pintype "passive"))
      (node (ref "C31") (pin "2") (pintype "passive"))
      (node (ref "C32") (pin "2") (pintype "passive"))
      (node (ref "C33") (pin "2") (pintype "passive"))
      (node (ref "C34") (pin "2") (pintype "passive"))
      (node (ref "C35") (pin "2") (pintype "passive"))
      (node (ref "C36") (pin "2") (pinfunction "2_2") (pintype "passive"))
      (node (ref "C41") (pin "2") (pinfunction "2_2") (pintype "passive"))
      (node (ref "LMX2571") (pin "1") (pinfunction "1_1") (pintype "passive"))
      (node (ref "M1") (pin "J1_58") (pinfunction "VCC5_J1_58") (pintype "passive"))
      (node (ref "M1") (pin "J1_59") (pinfunction "VCC5_J1_59") (pintype "passive"))
      (node (ref "M1") (pin "J1_60") (pinfunction "VCC5_J1_60") (pintype "passive"))
      (node (ref "R11") (pin "1") (pintype "passive"))
      (node (ref "TFTLCD") (pin "28") (pinfunction "BL_VDD_28") (pintype "passive"))
      (node (ref "TPS-3V3") (pin "13") (pinfunction "EN_13") (pintype "input"))
      (node (ref "TPS-3V3") (pin "15") (pinfunction "IN_15") (pintype "power_in"))
      (node (ref "TPS-3V3") (pin "16") (pinfunction "IN_16") (pintype "power_in"))
      (node (ref "TPS-5V") (pin "1") (pinfunction "OUT_1") (pintype "power_in"))
      (node (ref "TPS-5V") (pin "20") (pinfunction "OUT_20") (pintype "power_in"))
      (node (ref "TPS-5V") (pin "3") (pinfunction "SENSE_FB_3") (pintype "input"))
      (node (ref "串口屏") (pin "4") (pinfunction "4_4") (pintype "passive"))
    )
    (net (code "150") (name "VCC1") (class "Default")
      (node (ref "C8") (pin "2") (pintype "passive"))
      (node (ref "C9") (pin "2") (pintype "passive"))
      (node (ref "SUPPLY") (pin "2") (pinfunction "COM2_2") (pintype "passive"))
      (node (ref "SUPPLY") (pin "5") (pinfunction "COM2_5") (pintype "passive"))
      (node (ref "TPS-5V") (pin "13") (pinfunction "EN_13") (pintype "input"))
      (node (ref "TPS-5V") (pin "15") (pinfunction "IN_15") (pintype "power_in"))
      (node (ref "TPS-5V") (pin "16") (pinfunction "IN_16") (pintype "power_in"))
    )
    (net (code "151") (name "unconnected-(ADS1256-Pad2)") (class "Default")
      (node (ref "ADS1256") (pin "2") (pinfunction "2_2") (pintype "passive+no_connect"))
    )
    (net (code "152") (name "unconnected-(CH340-CTS-Pad9)") (class "Default")
      (node (ref "CH340") (pin "9") (pinfunction "CTS_9") (pintype "passive+no_connect"))
    )
    (net (code "153") (name "unconnected-(CH340-DCD-Pad12)") (class "Default")
      (node (ref "CH340") (pin "12") (pinfunction "DCD_12") (pintype "passive+no_connect"))
    )
    (net (code "154") (name "unconnected-(CH340-DSR-Pad10)") (class "Default")
      (node (ref "CH340") (pin "10") (pinfunction "DSR_10") (pintype "passive+no_connect"))
    )
    (net (code "155") (name "unconnected-(CH340-RI-Pad11)") (class "Default")
      (node (ref "CH340") (pin "11") (pinfunction "RI_11") (pintype "passive+no_connect"))
    )
    (net (code "156") (name "unconnected-(CH340-RS232-Pad15)") (class "Default")
      (node (ref "CH340") (pin "15") (pinfunction "RS232_15") (pintype "passive+no_connect"))
    )
    (net (code "157") (name "unconnected-(J2-K-Pad9)") (class "Default")
      (node (ref "J2") (pin "9") (pinfunction "K_9") (pintype "passive+no_connect"))
    )
    (net (code "158") (name "unconnected-(M1-VBAT-PadJ1_29)") (class "Default")
      (node (ref "M1") (pin "J1_29") (pinfunction "VBAT_J1_29") (pintype "passive+no_connect"))
    )
    (net (code "159") (name "unconnected-(ST-LINK-Pad6)") (class "Default")
      (node (ref "ST-LINK") (pin "6") (pinfunction "6_6") (pintype "passive+no_connect"))
    )
    (net (code "160") (name "unconnected-(ST-LINK-Pad9)") (class "Default")
      (node (ref "ST-LINK") (pin "9") (pinfunction "9_9") (pintype "passive+no_connect"))
    )
    (net (code "161") (name "unconnected-(ST-LINK-Pad10)") (class "Default")
      (node (ref "ST-LINK") (pin "10") (pinfunction "10_10") (pintype "passive+no_connect"))
    )
    (net (code "162") (name "unconnected-(SUPPLY-NC1-Pad1)") (class "Default")
      (node (ref "SUPPLY") (pin "1") (pinfunction "NC1_1") (pintype "passive"))
    )
    (net (code "163") (name "unconnected-(SUPPLY-NO2-Pad4)") (class "Default")
      (node (ref "SUPPLY") (pin "4") (pinfunction "NO2_4") (pintype "passive"))
    )
    (net (code "164") (name "unconnected-(TFTLCD-MO-Pad32)") (class "Default")
      (node (ref "TFTLCD") (pin "32") (pinfunction "MO_32") (pintype "passive+no_connect"))
    )
    (net (code "165") (name "unconnected-(TPS-3V3-0P4V-Pad10)") (class "Default")
      (node (ref "TPS-3V3") (pin "10") (pinfunction "0P4V_10") (pintype "passive+no_connect"))
    )
    (net (code "166") (name "unconnected-(TPS-3V3-0P8V-Pad9)") (class "Default")
      (node (ref "TPS-3V3") (pin "9") (pinfunction "0P8V_9") (pintype "passive+no_connect"))
    )
    (net (code "167") (name "unconnected-(TPS-3V3-3P2V-Pad6)") (class "Default")
      (node (ref "TPS-3V3") (pin "6") (pinfunction "3P2V_6") (pintype "passive+no_connect"))
    )
    (net (code "168") (name "unconnected-(TPS-3V3-6P4V1-Pad5)") (class "Default")
      (node (ref "TPS-3V3") (pin "5") (pinfunction "6P4V1_5") (pintype "passive+no_connect"))
    )
    (net (code "169") (name "unconnected-(TPS-3V3-6P4V2-Pad4)") (class "Default")
      (node (ref "TPS-3V3") (pin "4") (pinfunction "6P4V2_4") (pintype "passive+no_connect"))
    )
    (net (code "170") (name "unconnected-(TPS-3V3-NC-Pad2)") (class "Default")
      (node (ref "TPS-3V3") (pin "2") (pinfunction "NC_2") (pintype "passive+no_connect"))
    )
    (net (code "171") (name "unconnected-(TPS-3V3-NC-Pad17)") (class "Default")
      (node (ref "TPS-3V3") (pin "17") (pinfunction "NC_17") (pintype "passive+no_connect"))
    )
    (net (code "172") (name "unconnected-(TPS-3V3-NC-Pad18)") (class "Default")
      (node (ref "TPS-3V3") (pin "18") (pinfunction "NC_18") (pintype "passive+no_connect"))
    )
    (net (code "173") (name "unconnected-(TPS-3V3-NC-Pad19)") (class "Default")
      (node (ref "TPS-3V3") (pin "19") (pinfunction "NC_19") (pintype "passive+no_connect"))
    )
    (net (code "174") (name "unconnected-(TPS-5V-0P1V-Pad12)") (class "Default")
      (node (ref "TPS-5V") (pin "12") (pinfunction "0P1V_12") (pintype "passive+no_connect"))
    )
    (net (code "175") (name "unconnected-(TPS-5V-0P2V-Pad11)") (class "Default")
      (node (ref "TPS-5V") (pin "11") (pinfunction "0P2V_11") (pintype "passive+no_connect"))
    )
    (net (code "176") (name "unconnected-(TPS-5V-0P8V-Pad9)") (class "Default")
      (node (ref "TPS-5V") (pin "9") (pinfunction "0P8V_9") (pintype "passive+no_connect"))
    )
    (net (code "177") (name "unconnected-(TPS-5V-1P6V-Pad8)") (class "Default")
      (node (ref "TPS-5V") (pin "8") (pinfunction "1P6V_8") (pintype "passive+no_connect"))
    )
    (net (code "178") (name "unconnected-(TPS-5V-6P4V1-Pad5)") (class "Default")
      (node (ref "TPS-5V") (pin "5") (pinfunction "6P4V1_5") (pintype "passive+no_connect"))
    )
    (net (code "179") (name "unconnected-(TPS-5V-6P4V2-Pad4)") (class "Default")
      (node (ref "TPS-5V") (pin "4") (pinfunction "6P4V2_4") (pintype "passive+no_connect"))
    )
    (net (code "180") (name "unconnected-(TPS-5V-NC-Pad2)") (class "Default")
      (node (ref "TPS-5V") (pin "2") (pinfunction "NC_2") (pintype "passive+no_connect"))
    )
    (net (code "181") (name "unconnected-(TPS-5V-NC-Pad17)") (class "Default")
      (node (ref "TPS-5V") (pin "17") (pinfunction "NC_17") (pintype "passive+no_connect"))
    )
    (net (code "182") (name "unconnected-(TPS-5V-NC-Pad18)") (class "Default")
      (node (ref "TPS-5V") (pin "18") (pinfunction "NC_18") (pintype "passive+no_connect"))
    )
    (net (code "183") (name "unconnected-(TPS-5V-NC-Pad19)") (class "Default")
      (node (ref "TPS-5V") (pin "19") (pinfunction "NC_19") (pintype "passive+no_connect"))
    )
  )
)
